# Kord_Kontroller_PCB_0_1.net
KiCad netlist of a schematic drawn in EAGLE
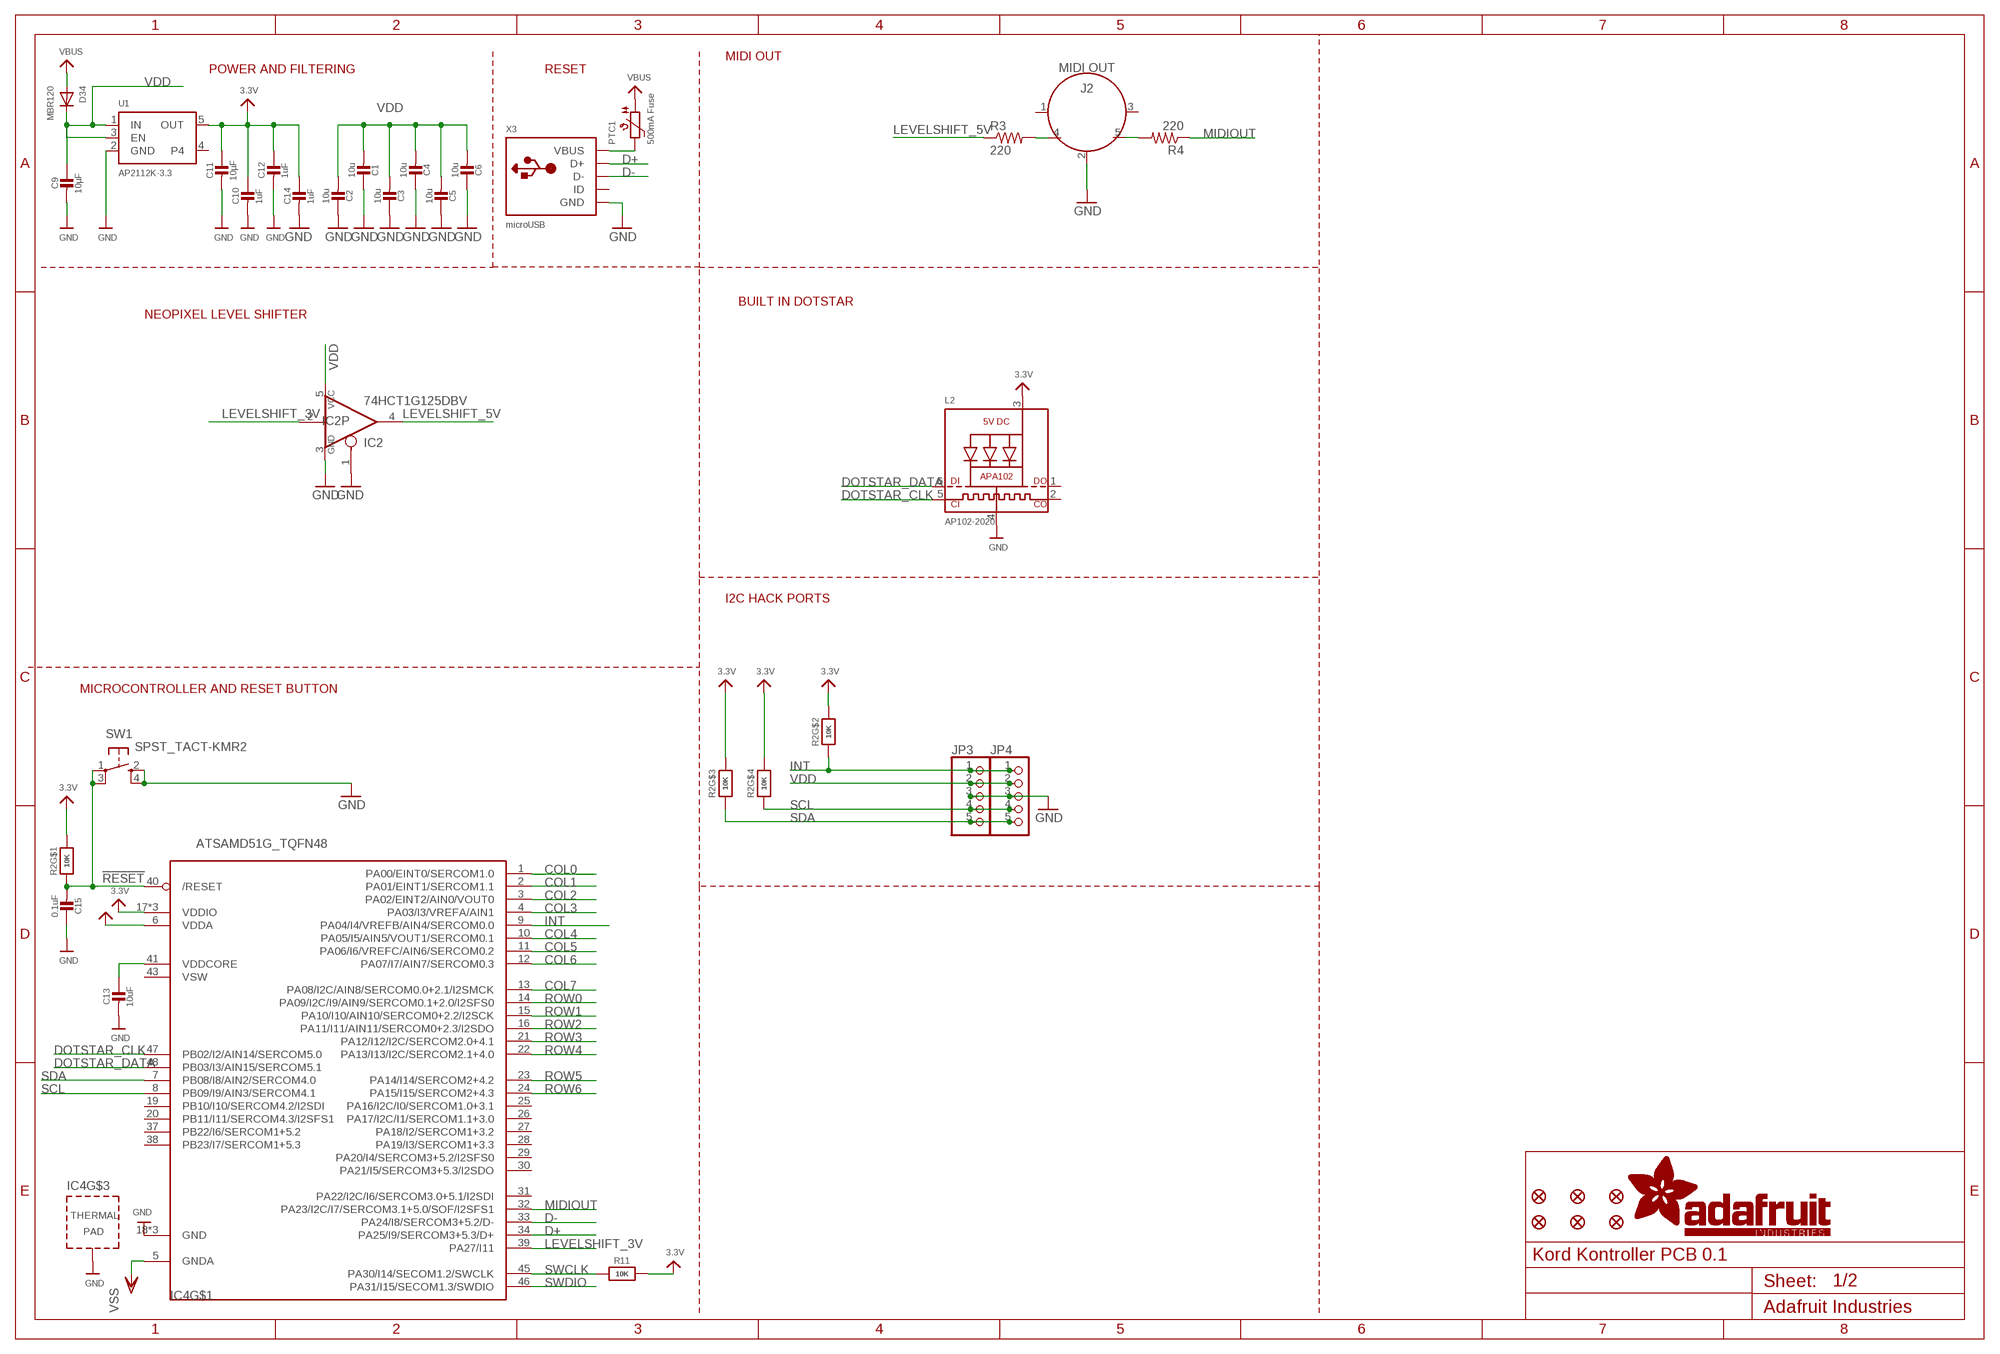
[diagram p0: schematic, sheet 1]
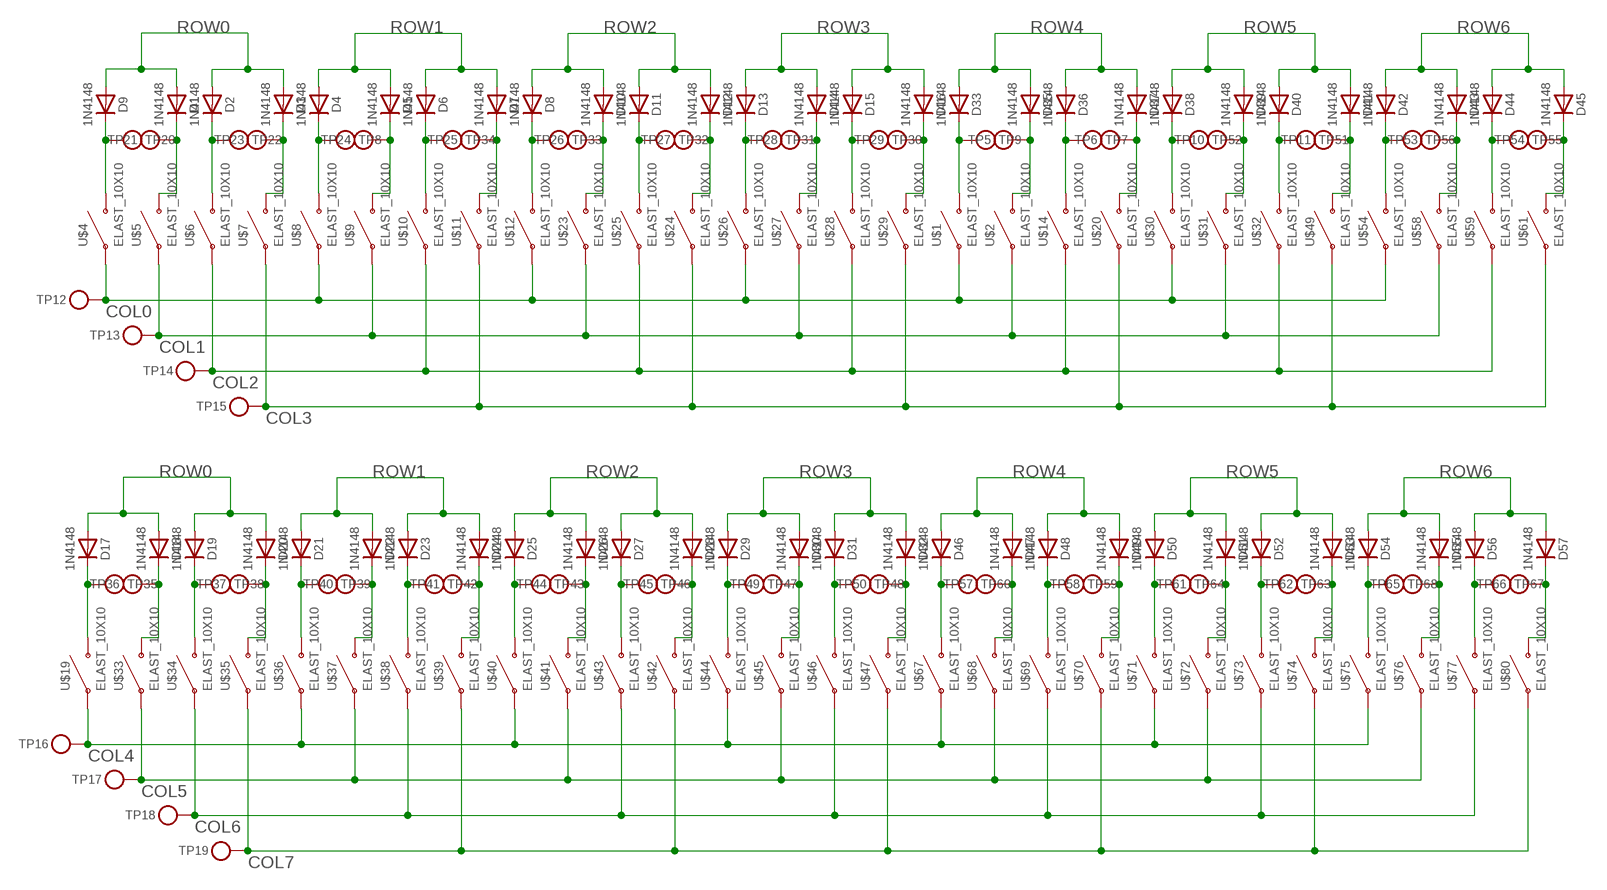
[diagram p1: schematic, sheet 2, part 1 of 2]
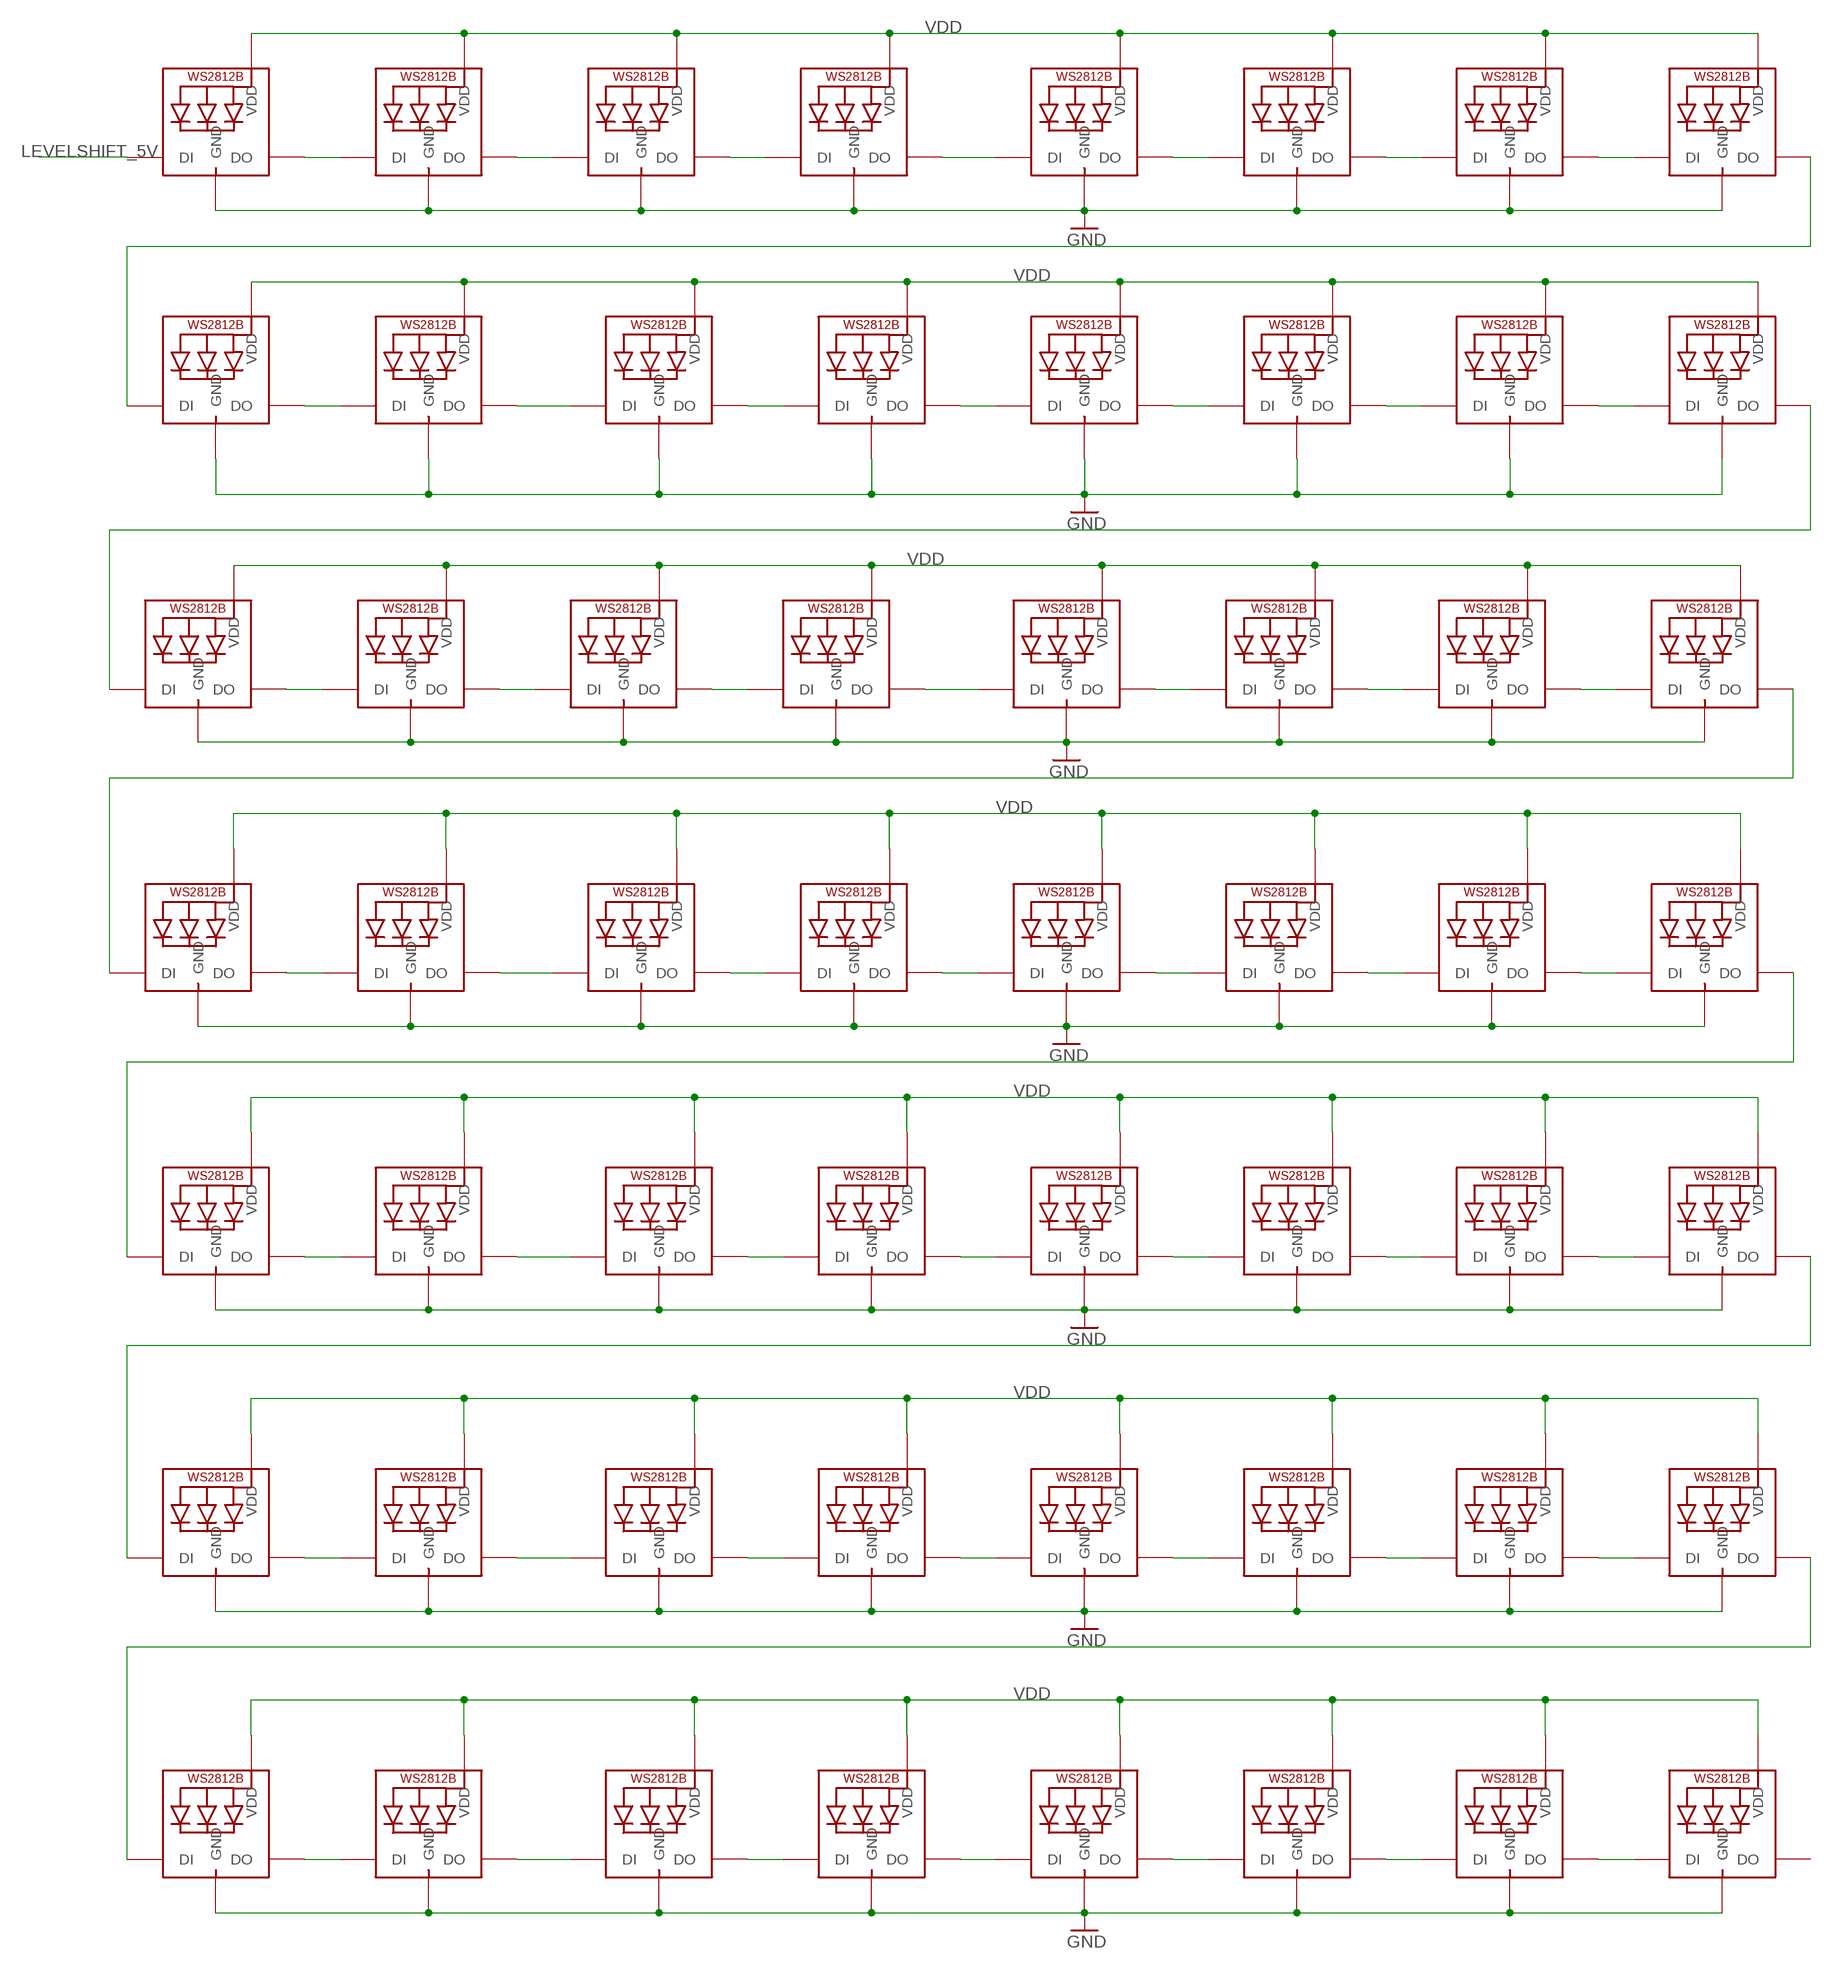
[diagram p2: schematic, sheet 2, part 2 of 2]

(export (version "E")
  (design (tool "Eeschema 10.0.6"))
  (components
    (comp (ref "C1")
      (value "10u")
      (footprint "eagle-import:0805-NO")
      (libsource (lib "eagle-import") (part "CAP_CERAMIC0805-NOOUTLINE"))
    )
    (comp (ref "C2")
      (value "10u")
      (footprint "eagle-import:0805-NO")
      (libsource (lib "eagle-import") (part "CAP_CERAMIC0805-NOOUTLINE"))
    )
    (comp (ref "C3")
      (value "10u")
      (footprint "eagle-import:0805-NO")
      (libsource (lib "eagle-import") (part "CAP_CERAMIC0805-NOOUTLINE"))
    )
    (comp (ref "C4")
      (value "10u")
      (footprint "eagle-import:0805-NO")
      (libsource (lib "eagle-import") (part "CAP_CERAMIC0805-NOOUTLINE"))
    )
    (comp (ref "C5")
      (value "10u")
      (footprint "eagle-import:0805-NO")
      (libsource (lib "eagle-import") (part "CAP_CERAMIC0805-NOOUTLINE"))
    )
    (comp (ref "C6")
      (value "10u")
      (footprint "eagle-import:0805-NO")
      (libsource (lib "eagle-import") (part "CAP_CERAMIC0805-NOOUTLINE"))
    )
    (comp (ref "C9")
      (value "10µF")
      (footprint "eagle-import:0805-NO")
      (libsource (lib "eagle-import") (part "CAP_CERAMIC0805-NOOUTLINE"))
    )
    (comp (ref "C10")
      (value "1uF")
      (footprint "eagle-import:0603-NO")
      (libsource (lib "eagle-import") (part "CAP_CERAMIC0603_NO"))
    )
    (comp (ref "C11")
      (value "10µF")
      (footprint "eagle-import:0805-NO")
      (libsource (lib "eagle-import") (part "CAP_CERAMIC0805-NOOUTLINE"))
    )
    (comp (ref "C12")
      (value "1uF")
      (footprint "eagle-import:0603-NO")
      (libsource (lib "eagle-import") (part "CAP_CERAMIC0603_NO"))
    )
    (comp (ref "C13")
      (value "10uF")
      (footprint "eagle-import:0805-NO")
      (libsource (lib "eagle-import") (part "CAP_CERAMIC0805-NOOUTLINE"))
    )
    (comp (ref "C14")
      (value "1uF")
      (footprint "eagle-import:0603-NO")
      (libsource (lib "eagle-import") (part "CAP_CERAMIC0603_NO"))
    )
    (comp (ref "C15")
      (value "0.1uF")
      (footprint "eagle-import:0603-NO")
      (libsource (lib "eagle-import") (part "CAP_CERAMIC0603_NO"))
    )
    (comp (ref "D34")
      (value "MBR120")
      (footprint "eagle-import:SOD-123FL")
      (libsource (lib "eagle-import") (part "DIODE_SOD-123FL"))
    )
    (comp (ref "FID1")
      (value "FIDUCIAL_1MM")
      (footprint "eagle-import:FIDUCIAL_1MM")
      (libsource (lib "eagle-import") (part "FIDUCIAL_1MM"))
    )
    (comp (ref "FID2")
      (value "FIDUCIAL_1MM")
      (footprint "eagle-import:FIDUCIAL_1MM")
      (libsource (lib "eagle-import") (part "FIDUCIAL_1MM"))
    )
    (comp (ref "FID3")
      (value "FIDUCIAL_1MM")
      (footprint "eagle-import:FIDUCIAL_1MM")
      (libsource (lib "eagle-import") (part "FIDUCIAL_1MM"))
    )
    (comp (ref "FID4")
      (value "FIDUCIAL_1MM")
      (footprint "eagle-import:FIDUCIAL_1MM")
      (libsource (lib "eagle-import") (part "FIDUCIAL_1MM"))
    )
    (comp (ref "FID5")
      (value "FIDUCIAL_1MM")
      (footprint "eagle-import:FIDUCIAL_1MM")
      (libsource (lib "eagle-import") (part "FIDUCIAL_1MM"))
    )
    (comp (ref "FID6")
      (value "FIDUCIAL_1MM")
      (footprint "eagle-import:FIDUCIAL_1MM")
      (libsource (lib "eagle-import") (part "FIDUCIAL_1MM"))
    )
    (comp (ref "IC2")
      (value "74HCT1G125DBV")
      (footprint "eagle-import:SOT23-5")
      (libsource (lib "eagle-import") (part "741G125DBVAHC"))
    )
    (comp (ref "IC4")
      (value "ATSAMD51G_TQFN48")
      (footprint "eagle-import:TQFN48_7MM")
      (libsource (lib "eagle-import") (part "ATSAMD51G_TQFN48"))
    )
    (comp (ref "J2")
      (value "MIDI OUT")
      (footprint "eagle-import:5-PIN-DIN-RA-PCB-NEW")
      (libsource (lib "eagle-import") (part "5-PIN-CIRCULAR-DINNEW"))
    )
    (comp (ref "JP3")
      (value "HEADER-1X5EDGESMT")
      (footprint "eagle-import:5P_EDGECONNECT")
      (libsource (lib "eagle-import") (part "HEADER-1X5EDGESMT"))
    )
    (comp (ref "JP4")
      (value "HEADER-1X5EDGESMT")
      (footprint "eagle-import:5P_EDGECONNECT")
      (libsource (lib "eagle-import") (part "HEADER-1X5EDGESMT"))
    )
    (comp (ref "L2")
      (value "AP102-2020")
      (footprint "eagle-import:APA102_2020")
      (libsource (lib "eagle-import") (part "APA1022020"))
    )
    (comp (ref "PTC1")
      (value "500mA Fuse")
      (footprint "eagle-import:1206")
      (libsource (lib "eagle-import") (part "PTC1206"))
    )
    (comp (ref "R2")
      (value "10K")
      (footprint "eagle-import:RESPACK_4X0603")
      (libsource (lib "eagle-import") (part "RESISTOR_4PACK"))
    )
    (comp (ref "R3")
      (value "220")
      (footprint "eagle-import:0603-RES")
      (libsource (lib "eagle-import") (part "220OHM-1/10W-1%(0603)"))
    )
    (comp (ref "R4")
      (value "220")
      (footprint "eagle-import:0603-RES")
      (libsource (lib "eagle-import") (part "220OHM-1/10W-1%(0603)"))
    )
    (comp (ref "R11")
      (value "10K")
      (footprint "eagle-import:0603-NO")
      (libsource (lib "eagle-import") (part "RESISTOR_0603_NOOUT"))
    )
    (comp (ref "SW1")
      (value "SPST_TACT-KMR2")
      (footprint "eagle-import:KMR2")
      (libsource (lib "eagle-import") (part "SPST_TACT-KMR2"))
    )
    (comp (ref "U1")
      (value "AP2112K-3.3")
      (footprint "eagle-import:SOT23-5")
      (libsource (lib "eagle-import") (part "VREG_SOT23-5"))
    )
    (comp (ref "X3")
      (value "microUSB")
      (footprint "eagle-import:4UCONN_20329_NARROW")
      (libsource (lib "eagle-import") (part "USB_MICRO_NARROW"))
    )
    (comp (ref "D1")
      (value "1N4148")
      (footprint "eagle-import:SOD-323")
      (libsource (lib "eagle-import") (part "DIODESOD-323"))
    )
    (comp (ref "D2")
      (value "1N4148")
      (footprint "eagle-import:SOD-323")
      (libsource (lib "eagle-import") (part "DIODESOD-323"))
    )
    (comp (ref "D3")
      (value "1N4148")
      (footprint "eagle-import:SOD-323")
      (libsource (lib "eagle-import") (part "DIODESOD-323"))
    )
    (comp (ref "D4")
      (value "1N4148")
      (footprint "eagle-import:SOD-323")
      (libsource (lib "eagle-import") (part "DIODESOD-323"))
    )
    (comp (ref "D5")
      (value "1N4148")
      (footprint "eagle-import:SOD-323")
      (libsource (lib "eagle-import") (part "DIODESOD-323"))
    )
    (comp (ref "D6")
      (value "1N4148")
      (footprint "eagle-import:SOD-323")
      (libsource (lib "eagle-import") (part "DIODESOD-323"))
    )
    (comp (ref "D7")
      (value "1N4148")
      (footprint "eagle-import:SOD-323")
      (libsource (lib "eagle-import") (part "DIODESOD-323"))
    )
    (comp (ref "D8")
      (value "1N4148")
      (footprint "eagle-import:SOD-323")
      (libsource (lib "eagle-import") (part "DIODESOD-323"))
    )
    (comp (ref "D9")
      (value "1N4148")
      (footprint "eagle-import:SOD-323")
      (libsource (lib "eagle-import") (part "DIODESOD-323"))
    )
    (comp (ref "D10")
      (value "1N4148")
      (footprint "eagle-import:SOD-323")
      (libsource (lib "eagle-import") (part "DIODESOD-323"))
    )
    (comp (ref "D11")
      (value "1N4148")
      (footprint "eagle-import:SOD-323")
      (libsource (lib "eagle-import") (part "DIODESOD-323"))
    )
    (comp (ref "D12")
      (value "1N4148")
      (footprint "eagle-import:SOD-323")
      (libsource (lib "eagle-import") (part "DIODESOD-323"))
    )
    (comp (ref "D13")
      (value "1N4148")
      (footprint "eagle-import:SOD-323")
      (libsource (lib "eagle-import") (part "DIODESOD-323"))
    )
    (comp (ref "D14")
      (value "1N4148")
      (footprint "eagle-import:SOD-323")
      (libsource (lib "eagle-import") (part "DIODESOD-323"))
    )
    (comp (ref "D15")
      (value "1N4148")
      (footprint "eagle-import:SOD-323")
      (libsource (lib "eagle-import") (part "DIODESOD-323"))
    )
    (comp (ref "D16")
      (value "1N4148")
      (footprint "eagle-import:SOD-323")
      (libsource (lib "eagle-import") (part "DIODESOD-323"))
    )
    (comp (ref "D17")
      (value "1N4148")
      (footprint "eagle-import:SOD-323")
      (libsource (lib "eagle-import") (part "DIODESOD-323"))
    )
    (comp (ref "D18")
      (value "1N4148")
      (footprint "eagle-import:SOD-323")
      (libsource (lib "eagle-import") (part "DIODESOD-323"))
    )
    (comp (ref "D19")
      (value "1N4148")
      (footprint "eagle-import:SOD-323")
      (libsource (lib "eagle-import") (part "DIODESOD-323"))
    )
    (comp (ref "D20")
      (value "1N4148")
      (footprint "eagle-import:SOD-323")
      (libsource (lib "eagle-import") (part "DIODESOD-323"))
    )
    (comp (ref "D21")
      (value "1N4148")
      (footprint "eagle-import:SOD-323")
      (libsource (lib "eagle-import") (part "DIODESOD-323"))
    )
    (comp (ref "D22")
      (value "1N4148")
      (footprint "eagle-import:SOD-323")
      (libsource (lib "eagle-import") (part "DIODESOD-323"))
    )
    (comp (ref "D23")
      (value "1N4148")
      (footprint "eagle-import:SOD-323")
      (libsource (lib "eagle-import") (part "DIODESOD-323"))
    )
    (comp (ref "D24")
      (value "1N4148")
      (footprint "eagle-import:SOD-323")
      (libsource (lib "eagle-import") (part "DIODESOD-323"))
    )
    (comp (ref "D25")
      (value "1N4148")
      (footprint "eagle-import:SOD-323")
      (libsource (lib "eagle-import") (part "DIODESOD-323"))
    )
    (comp (ref "D26")
      (value "1N4148")
      (footprint "eagle-import:SOD-323")
      (libsource (lib "eagle-import") (part "DIODESOD-323"))
    )
    (comp (ref "D27")
      (value "1N4148")
      (footprint "eagle-import:SOD-323")
      (libsource (lib "eagle-import") (part "DIODESOD-323"))
    )
    (comp (ref "D28")
      (value "1N4148")
      (footprint "eagle-import:SOD-323")
      (libsource (lib "eagle-import") (part "DIODESOD-323"))
    )
    (comp (ref "D29")
      (value "1N4148")
      (footprint "eagle-import:SOD-323")
      (libsource (lib "eagle-import") (part "DIODESOD-323"))
    )
    (comp (ref "D30")
      (value "1N4148")
      (footprint "eagle-import:SOD-323")
      (libsource (lib "eagle-import") (part "DIODESOD-323"))
    )
    (comp (ref "D31")
      (value "1N4148")
      (footprint "eagle-import:SOD-323")
      (libsource (lib "eagle-import") (part "DIODESOD-323"))
    )
    (comp (ref "D32")
      (value "1N4148")
      (footprint "eagle-import:SOD-323")
      (libsource (lib "eagle-import") (part "DIODESOD-323"))
    )
    (comp (ref "D33")
      (value "1N4148")
      (footprint "eagle-import:SOD-323")
      (libsource (lib "eagle-import") (part "DIODESOD-323"))
    )
    (comp (ref "D35")
      (value "1N4148")
      (footprint "eagle-import:SOD-323")
      (libsource (lib "eagle-import") (part "DIODESOD-323"))
    )
    (comp (ref "D36")
      (value "1N4148")
      (footprint "eagle-import:SOD-323")
      (libsource (lib "eagle-import") (part "DIODESOD-323"))
    )
    (comp (ref "D37")
      (value "1N4148")
      (footprint "eagle-import:SOD-323")
      (libsource (lib "eagle-import") (part "DIODESOD-323"))
    )
    (comp (ref "D38")
      (value "1N4148")
      (footprint "eagle-import:SOD-323")
      (libsource (lib "eagle-import") (part "DIODESOD-323"))
    )
    (comp (ref "D39")
      (value "1N4148")
      (footprint "eagle-import:SOD-323")
      (libsource (lib "eagle-import") (part "DIODESOD-323"))
    )
    (comp (ref "D40")
      (value "1N4148")
      (footprint "eagle-import:SOD-323")
      (libsource (lib "eagle-import") (part "DIODESOD-323"))
    )
    (comp (ref "D41")
      (value "1N4148")
      (footprint "eagle-import:SOD-323")
      (libsource (lib "eagle-import") (part "DIODESOD-323"))
    )
    (comp (ref "D42")
      (value "1N4148")
      (footprint "eagle-import:SOD-323")
      (libsource (lib "eagle-import") (part "DIODESOD-323"))
    )
    (comp (ref "D43")
      (value "1N4148")
      (footprint "eagle-import:SOD-323")
      (libsource (lib "eagle-import") (part "DIODESOD-323"))
    )
    (comp (ref "D44")
      (value "1N4148")
      (footprint "eagle-import:SOD-323")
      (libsource (lib "eagle-import") (part "DIODESOD-323"))
    )
    (comp (ref "D45")
      (value "1N4148")
      (footprint "eagle-import:SOD-323")
      (libsource (lib "eagle-import") (part "DIODESOD-323"))
    )
    (comp (ref "D46")
      (value "1N4148")
      (footprint "eagle-import:SOD-323")
      (libsource (lib "eagle-import") (part "DIODESOD-323"))
    )
    (comp (ref "D47")
      (value "1N4148")
      (footprint "eagle-import:SOD-323")
      (libsource (lib "eagle-import") (part "DIODESOD-323"))
    )
    (comp (ref "D48")
      (value "1N4148")
      (footprint "eagle-import:SOD-323")
      (libsource (lib "eagle-import") (part "DIODESOD-323"))
    )
    (comp (ref "D49")
      (value "1N4148")
      (footprint "eagle-import:SOD-323")
      (libsource (lib "eagle-import") (part "DIODESOD-323"))
    )
    (comp (ref "D50")
      (value "1N4148")
      (footprint "eagle-import:SOD-323")
      (libsource (lib "eagle-import") (part "DIODESOD-323"))
    )
    (comp (ref "D51")
      (value "1N4148")
      (footprint "eagle-import:SOD-323")
      (libsource (lib "eagle-import") (part "DIODESOD-323"))
    )
    (comp (ref "D52")
      (value "1N4148")
      (footprint "eagle-import:SOD-323")
      (libsource (lib "eagle-import") (part "DIODESOD-323"))
    )
    (comp (ref "D53")
      (value "1N4148")
      (footprint "eagle-import:SOD-323")
      (libsource (lib "eagle-import") (part "DIODESOD-323"))
    )
    (comp (ref "D54")
      (value "1N4148")
      (footprint "eagle-import:SOD-323")
      (libsource (lib "eagle-import") (part "DIODESOD-323"))
    )
    (comp (ref "D55")
      (value "1N4148")
      (footprint "eagle-import:SOD-323")
      (libsource (lib "eagle-import") (part "DIODESOD-323"))
    )
    (comp (ref "D56")
      (value "1N4148")
      (footprint "eagle-import:SOD-323")
      (libsource (lib "eagle-import") (part "DIODESOD-323"))
    )
    (comp (ref "D57")
      (value "1N4148")
      (footprint "eagle-import:SOD-323")
      (libsource (lib "eagle-import") (part "DIODESOD-323"))
    )
    (comp (ref "LED1")
      (value "WS2812B3535")
      (footprint "eagle-import:LED3535")
      (libsource (lib "eagle-import") (part "WS2812B3535"))
    )
    (comp (ref "LED2")
      (value "WS2812B3535")
      (footprint "eagle-import:LED3535")
      (libsource (lib "eagle-import") (part "WS2812B3535"))
    )
    (comp (ref "LED3")
      (value "WS2812B3535")
      (footprint "eagle-import:LED3535")
      (libsource (lib "eagle-import") (part "WS2812B3535"))
    )
    (comp (ref "LED4")
      (value "WS2812B3535")
      (footprint "eagle-import:LED3535")
      (libsource (lib "eagle-import") (part "WS2812B3535"))
    )
    (comp (ref "LED5")
      (value "WS2812B3535")
      (footprint "eagle-import:LED3535")
      (libsource (lib "eagle-import") (part "WS2812B3535"))
    )
    (comp (ref "LED6")
      (value "WS2812B3535")
      (footprint "eagle-import:LED3535")
      (libsource (lib "eagle-import") (part "WS2812B3535"))
    )
    (comp (ref "LED7")
      (value "WS2812B3535")
      (footprint "eagle-import:LED3535")
      (libsource (lib "eagle-import") (part "WS2812B3535"))
    )
    (comp (ref "LED8")
      (value "WS2812B3535")
      (footprint "eagle-import:LED3535")
      (libsource (lib "eagle-import") (part "WS2812B3535"))
    )
    (comp (ref "LED9")
      (value "WS2812B3535")
      (footprint "eagle-import:LED3535")
      (libsource (lib "eagle-import") (part "WS2812B3535"))
    )
    (comp (ref "LED10")
      (value "WS2812B3535")
      (footprint "eagle-import:LED3535")
      (libsource (lib "eagle-import") (part "WS2812B3535"))
    )
    (comp (ref "LED11")
      (value "WS2812B3535")
      (footprint "eagle-import:LED3535")
      (libsource (lib "eagle-import") (part "WS2812B3535"))
    )
    (comp (ref "LED12")
      (value "WS2812B3535")
      (footprint "eagle-import:LED3535")
      (libsource (lib "eagle-import") (part "WS2812B3535"))
    )
    (comp (ref "LED13")
      (value "WS2812B3535")
      (footprint "eagle-import:LED3535")
      (libsource (lib "eagle-import") (part "WS2812B3535"))
    )
    (comp (ref "LED14")
      (value "WS2812B3535")
      (footprint "eagle-import:LED3535")
      (libsource (lib "eagle-import") (part "WS2812B3535"))
    )
    (comp (ref "LED15")
      (value "WS2812B3535")
      (footprint "eagle-import:LED3535")
      (libsource (lib "eagle-import") (part "WS2812B3535"))
    )
    (comp (ref "LED16")
      (value "WS2812B3535")
      (footprint "eagle-import:LED3535")
      (libsource (lib "eagle-import") (part "WS2812B3535"))
    )
    (comp (ref "LED17")
      (value "WS2812B3535")
      (footprint "eagle-import:LED3535")
      (libsource (lib "eagle-import") (part "WS2812B3535"))
    )
    (comp (ref "LED18")
      (value "WS2812B3535")
      (footprint "eagle-import:LED3535")
      (libsource (lib "eagle-import") (part "WS2812B3535"))
    )
    (comp (ref "LED19")
      (value "WS2812B3535")
      (footprint "eagle-import:LED3535")
      (libsource (lib "eagle-import") (part "WS2812B3535"))
    )
    (comp (ref "LED20")
      (value "WS2812B3535")
      (footprint "eagle-import:LED3535")
      (libsource (lib "eagle-import") (part "WS2812B3535"))
    )
    (comp (ref "LED21")
      (value "WS2812B3535")
      (footprint "eagle-import:LED3535")
      (libsource (lib "eagle-import") (part "WS2812B3535"))
    )
    (comp (ref "LED22")
      (value "WS2812B3535")
      (footprint "eagle-import:LED3535")
      (libsource (lib "eagle-import") (part "WS2812B3535"))
    )
    (comp (ref "LED23")
      (value "WS2812B3535")
      (footprint "eagle-import:LED3535")
      (libsource (lib "eagle-import") (part "WS2812B3535"))
    )
    (comp (ref "LED24")
      (value "WS2812B3535")
      (footprint "eagle-import:LED3535")
      (libsource (lib "eagle-import") (part "WS2812B3535"))
    )
    (comp (ref "LED25")
      (value "WS2812B3535")
      (footprint "eagle-import:LED3535")
      (libsource (lib "eagle-import") (part "WS2812B3535"))
    )
    (comp (ref "LED26")
      (value "WS2812B3535")
      (footprint "eagle-import:LED3535")
      (libsource (lib "eagle-import") (part "WS2812B3535"))
    )
    (comp (ref "LED27")
      (value "WS2812B3535")
      (footprint "eagle-import:LED3535")
      (libsource (lib "eagle-import") (part "WS2812B3535"))
    )
    (comp (ref "LED28")
      (value "WS2812B3535")
      (footprint "eagle-import:LED3535")
      (libsource (lib "eagle-import") (part "WS2812B3535"))
    )
    (comp (ref "LED29")
      (value "WS2812B3535")
      (footprint "eagle-import:LED3535")
      (libsource (lib "eagle-import") (part "WS2812B3535"))
    )
    (comp (ref "LED30")
      (value "WS2812B3535")
      (footprint "eagle-import:LED3535")
      (libsource (lib "eagle-import") (part "WS2812B3535"))
    )
    (comp (ref "LED31")
      (value "WS2812B3535")
      (footprint "eagle-import:LED3535")
      (libsource (lib "eagle-import") (part "WS2812B3535"))
    )
    (comp (ref "LED32")
      (value "WS2812B3535")
      (footprint "eagle-import:LED3535")
      (libsource (lib "eagle-import") (part "WS2812B3535"))
    )
    (comp (ref "LED33")
      (value "WS2812B3535")
      (footprint "eagle-import:LED3535")
      (libsource (lib "eagle-import") (part "WS2812B3535"))
    )
    (comp (ref "LED34")
      (value "WS2812B3535")
      (footprint "eagle-import:LED3535")
      (libsource (lib "eagle-import") (part "WS2812B3535"))
    )
    (comp (ref "LED35")
      (value "WS2812B3535")
      (footprint "eagle-import:LED3535")
      (libsource (lib "eagle-import") (part "WS2812B3535"))
    )
    (comp (ref "LED36")
      (value "WS2812B3535")
      (footprint "eagle-import:LED3535")
      (libsource (lib "eagle-import") (part "WS2812B3535"))
    )
    (comp (ref "LED37")
      (value "WS2812B3535")
      (footprint "eagle-import:LED3535")
      (libsource (lib "eagle-import") (part "WS2812B3535"))
    )
    (comp (ref "LED38")
      (value "WS2812B3535")
      (footprint "eagle-import:LED3535")
      (libsource (lib "eagle-import") (part "WS2812B3535"))
    )
    (comp (ref "LED39")
      (value "WS2812B3535")
      (footprint "eagle-import:LED3535")
      (libsource (lib "eagle-import") (part "WS2812B3535"))
    )
    (comp (ref "LED40")
      (value "WS2812B3535")
      (footprint "eagle-import:LED3535")
      (libsource (lib "eagle-import") (part "WS2812B3535"))
    )
    (comp (ref "LED41")
      (value "WS2812B3535")
      (footprint "eagle-import:LED3535")
      (libsource (lib "eagle-import") (part "WS2812B3535"))
    )
    (comp (ref "LED42")
      (value "WS2812B3535")
      (footprint "eagle-import:LED3535")
      (libsource (lib "eagle-import") (part "WS2812B3535"))
    )
    (comp (ref "LED43")
      (value "WS2812B3535")
      (footprint "eagle-import:LED3535")
      (libsource (lib "eagle-import") (part "WS2812B3535"))
    )
    (comp (ref "LED44")
      (value "WS2812B3535")
      (footprint "eagle-import:LED3535")
      (libsource (lib "eagle-import") (part "WS2812B3535"))
    )
    (comp (ref "LED45")
      (value "WS2812B3535")
      (footprint "eagle-import:LED3535")
      (libsource (lib "eagle-import") (part "WS2812B3535"))
    )
    (comp (ref "LED46")
      (value "WS2812B3535")
      (footprint "eagle-import:LED3535")
      (libsource (lib "eagle-import") (part "WS2812B3535"))
    )
    (comp (ref "LED47")
      (value "WS2812B3535")
      (footprint "eagle-import:LED3535")
      (libsource (lib "eagle-import") (part "WS2812B3535"))
    )
    (comp (ref "LED48")
      (value "WS2812B3535")
      (footprint "eagle-import:LED3535")
      (libsource (lib "eagle-import") (part "WS2812B3535"))
    )
    (comp (ref "LED49")
      (value "WS2812B3535")
      (footprint "eagle-import:LED3535")
      (libsource (lib "eagle-import") (part "WS2812B3535"))
    )
    (comp (ref "LED50")
      (value "WS2812B3535")
      (footprint "eagle-import:LED3535")
      (libsource (lib "eagle-import") (part "WS2812B3535"))
    )
    (comp (ref "LED51")
      (value "WS2812B3535")
      (footprint "eagle-import:LED3535")
      (libsource (lib "eagle-import") (part "WS2812B3535"))
    )
    (comp (ref "LED52")
      (value "WS2812B3535")
      (footprint "eagle-import:LED3535")
      (libsource (lib "eagle-import") (part "WS2812B3535"))
    )
    (comp (ref "LED53")
      (value "WS2812B3535")
      (footprint "eagle-import:LED3535")
      (libsource (lib "eagle-import") (part "WS2812B3535"))
    )
    (comp (ref "LED54")
      (value "WS2812B3535")
      (footprint "eagle-import:LED3535")
      (libsource (lib "eagle-import") (part "WS2812B3535"))
    )
    (comp (ref "LED55")
      (value "WS2812B3535")
      (footprint "eagle-import:LED3535")
      (libsource (lib "eagle-import") (part "WS2812B3535"))
    )
    (comp (ref "LED56")
      (value "WS2812B3535")
      (footprint "eagle-import:LED3535")
      (libsource (lib "eagle-import") (part "WS2812B3535"))
    )
    (comp (ref "TP5")
      (value "TESTPOINTROUND1.5MM")
      (footprint "eagle-import:TESTPOINT_ROUND_1.5MM")
      (libsource (lib "eagle-import") (part "TESTPOINTROUND1.5MM"))
    )
    (comp (ref "TP6")
      (value "TESTPOINTROUND1.5MM")
      (footprint "eagle-import:TESTPOINT_ROUND_1.5MM")
      (libsource (lib "eagle-import") (part "TESTPOINTROUND1.5MM"))
    )
    (comp (ref "TP7")
      (value "TESTPOINTROUND1.5MM")
      (footprint "eagle-import:TESTPOINT_ROUND_1.5MM")
      (libsource (lib "eagle-import") (part "TESTPOINTROUND1.5MM"))
    )
    (comp (ref "TP8")
      (value "TESTPOINTROUND1.5MM")
      (footprint "eagle-import:TESTPOINT_ROUND_1.5MM")
      (libsource (lib "eagle-import") (part "TESTPOINTROUND1.5MM"))
    )
    (comp (ref "TP9")
      (value "TESTPOINTROUND1.5MM")
      (footprint "eagle-import:TESTPOINT_ROUND_1.5MM")
      (libsource (lib "eagle-import") (part "TESTPOINTROUND1.5MM"))
    )
    (comp (ref "TP10")
      (value "TESTPOINTROUND1.5MM")
      (footprint "eagle-import:TESTPOINT_ROUND_1.5MM")
      (libsource (lib "eagle-import") (part "TESTPOINTROUND1.5MM"))
    )
    (comp (ref "TP11")
      (value "TESTPOINTROUND1.5MM")
      (footprint "eagle-import:TESTPOINT_ROUND_1.5MM")
      (libsource (lib "eagle-import") (part "TESTPOINTROUND1.5MM"))
    )
    (comp (ref "TP12")
      (value "TESTPOINTROUND1.5MM")
      (footprint "eagle-import:TESTPOINT_ROUND_1.5MM")
      (libsource (lib "eagle-import") (part "TESTPOINTROUND1.5MM"))
    )
    (comp (ref "TP13")
      (value "TESTPOINTROUND1.5MM")
      (footprint "eagle-import:TESTPOINT_ROUND_1.5MM")
      (libsource (lib "eagle-import") (part "TESTPOINTROUND1.5MM"))
    )
    (comp (ref "TP14")
      (value "TESTPOINTROUND1.5MM")
      (footprint "eagle-import:TESTPOINT_ROUND_1.5MM")
      (libsource (lib "eagle-import") (part "TESTPOINTROUND1.5MM"))
    )
    (comp (ref "TP15")
      (value "TESTPOINTROUND1.5MM")
      (footprint "eagle-import:TESTPOINT_ROUND_1.5MM")
      (libsource (lib "eagle-import") (part "TESTPOINTROUND1.5MM"))
    )
    (comp (ref "TP16")
      (value "TESTPOINTROUND1.5MM")
      (footprint "eagle-import:TESTPOINT_ROUND_1.5MM")
      (libsource (lib "eagle-import") (part "TESTPOINTROUND1.5MM"))
    )
    (comp (ref "TP17")
      (value "TESTPOINTROUND1.5MM")
      (footprint "eagle-import:TESTPOINT_ROUND_1.5MM")
      (libsource (lib "eagle-import") (part "TESTPOINTROUND1.5MM"))
    )
    (comp (ref "TP18")
      (value "TESTPOINTROUND1.5MM")
      (footprint "eagle-import:TESTPOINT_ROUND_1.5MM")
      (libsource (lib "eagle-import") (part "TESTPOINTROUND1.5MM"))
    )
    (comp (ref "TP19")
      (value "TESTPOINTROUND1.5MM")
      (footprint "eagle-import:TESTPOINT_ROUND_1.5MM")
      (libsource (lib "eagle-import") (part "TESTPOINTROUND1.5MM"))
    )
    (comp (ref "TP20")
      (value "TESTPOINTROUND1.5MM")
      (footprint "eagle-import:TESTPOINT_ROUND_1.5MM")
      (libsource (lib "eagle-import") (part "TESTPOINTROUND1.5MM"))
    )
    (comp (ref "TP21")
      (value "TESTPOINTROUND1.5MM")
      (footprint "eagle-import:TESTPOINT_ROUND_1.5MM")
      (libsource (lib "eagle-import") (part "TESTPOINTROUND1.5MM"))
    )
    (comp (ref "TP22")
      (value "TESTPOINTROUND1.5MM")
      (footprint "eagle-import:TESTPOINT_ROUND_1.5MM")
      (libsource (lib "eagle-import") (part "TESTPOINTROUND1.5MM"))
    )
    (comp (ref "TP23")
      (value "TESTPOINTROUND1.5MM")
      (footprint "eagle-import:TESTPOINT_ROUND_1.5MM")
      (libsource (lib "eagle-import") (part "TESTPOINTROUND1.5MM"))
    )
    (comp (ref "TP24")
      (value "TESTPOINTROUND1.5MM")
      (footprint "eagle-import:TESTPOINT_ROUND_1.5MM")
      (libsource (lib "eagle-import") (part "TESTPOINTROUND1.5MM"))
    )
    (comp (ref "TP25")
      (value "TESTPOINTROUND1.5MM")
      (footprint "eagle-import:TESTPOINT_ROUND_1.5MM")
      (libsource (lib "eagle-import") (part "TESTPOINTROUND1.5MM"))
    )
    (comp (ref "TP26")
      (value "TESTPOINTROUND1.5MM")
      (footprint "eagle-import:TESTPOINT_ROUND_1.5MM")
      (libsource (lib "eagle-import") (part "TESTPOINTROUND1.5MM"))
    )
    (comp (ref "TP27")
      (value "TESTPOINTROUND1.5MM")
      (footprint "eagle-import:TESTPOINT_ROUND_1.5MM")
      (libsource (lib "eagle-import") (part "TESTPOINTROUND1.5MM"))
    )
    (comp (ref "TP28")
      (value "TESTPOINTROUND1.5MM")
      (footprint "eagle-import:TESTPOINT_ROUND_1.5MM")
      (libsource (lib "eagle-import") (part "TESTPOINTROUND1.5MM"))
    )
    (comp (ref "TP29")
      (value "TESTPOINTROUND1.5MM")
      (footprint "eagle-import:TESTPOINT_ROUND_1.5MM")
      (libsource (lib "eagle-import") (part "TESTPOINTROUND1.5MM"))
    )
    (comp (ref "TP30")
      (value "TESTPOINTROUND1.5MM")
      (footprint "eagle-import:TESTPOINT_ROUND_1.5MM")
      (libsource (lib "eagle-import") (part "TESTPOINTROUND1.5MM"))
    )
    (comp (ref "TP31")
      (value "TESTPOINTROUND1.5MM")
      (footprint "eagle-import:TESTPOINT_ROUND_1.5MM")
      (libsource (lib "eagle-import") (part "TESTPOINTROUND1.5MM"))
    )
    (comp (ref "TP32")
      (value "TESTPOINTROUND1.5MM")
      (footprint "eagle-import:TESTPOINT_ROUND_1.5MM")
      (libsource (lib "eagle-import") (part "TESTPOINTROUND1.5MM"))
    )
    (comp (ref "TP33")
      (value "TESTPOINTROUND1.5MM")
      (footprint "eagle-import:TESTPOINT_ROUND_1.5MM")
      (libsource (lib "eagle-import") (part "TESTPOINTROUND1.5MM"))
    )
    (comp (ref "TP34")
      (value "TESTPOINTROUND1.5MM")
      (footprint "eagle-import:TESTPOINT_ROUND_1.5MM")
      (libsource (lib "eagle-import") (part "TESTPOINTROUND1.5MM"))
    )
    (comp (ref "TP35")
      (value "TESTPOINTROUND1.5MM")
      (footprint "eagle-import:TESTPOINT_ROUND_1.5MM")
      (libsource (lib "eagle-import") (part "TESTPOINTROUND1.5MM"))
    )
    (comp (ref "TP36")
      (value "TESTPOINTROUND1.5MM")
      (footprint "eagle-import:TESTPOINT_ROUND_1.5MM")
      (libsource (lib "eagle-import") (part "TESTPOINTROUND1.5MM"))
    )
    (comp (ref "TP37")
      (value "TESTPOINTROUND1.5MM")
      (footprint "eagle-import:TESTPOINT_ROUND_1.5MM")
      (libsource (lib "eagle-import") (part "TESTPOINTROUND1.5MM"))
    )
    (comp (ref "TP38")
      (value "TESTPOINTROUND1.5MM")
      (footprint "eagle-import:TESTPOINT_ROUND_1.5MM")
      (libsource (lib "eagle-import") (part "TESTPOINTROUND1.5MM"))
    )
    (comp (ref "TP39")
      (value "TESTPOINTROUND1.5MM")
      (footprint "eagle-import:TESTPOINT_ROUND_1.5MM")
      (libsource (lib "eagle-import") (part "TESTPOINTROUND1.5MM"))
    )
    (comp (ref "TP40")
      (value "TESTPOINTROUND1.5MM")
      (footprint "eagle-import:TESTPOINT_ROUND_1.5MM")
      (libsource (lib "eagle-import") (part "TESTPOINTROUND1.5MM"))
    )
    (comp (ref "TP41")
      (value "TESTPOINTROUND1.5MM")
      (footprint "eagle-import:TESTPOINT_ROUND_1.5MM")
      (libsource (lib "eagle-import") (part "TESTPOINTROUND1.5MM"))
    )
    (comp (ref "TP42")
      (value "TESTPOINTROUND1.5MM")
      (footprint "eagle-import:TESTPOINT_ROUND_1.5MM")
      (libsource (lib "eagle-import") (part "TESTPOINTROUND1.5MM"))
    )
    (comp (ref "TP43")
      (value "TESTPOINTROUND1.5MM")
      (footprint "eagle-import:TESTPOINT_ROUND_1.5MM")
      (libsource (lib "eagle-import") (part "TESTPOINTROUND1.5MM"))
    )
    (comp (ref "TP44")
      (value "TESTPOINTROUND1.5MM")
      (footprint "eagle-import:TESTPOINT_ROUND_1.5MM")
      (libsource (lib "eagle-import") (part "TESTPOINTROUND1.5MM"))
    )
    (comp (ref "TP45")
      (value "TESTPOINTROUND1.5MM")
      (footprint "eagle-import:TESTPOINT_ROUND_1.5MM")
      (libsource (lib "eagle-import") (part "TESTPOINTROUND1.5MM"))
    )
    (comp (ref "TP46")
      (value "TESTPOINTROUND1.5MM")
      (footprint "eagle-import:TESTPOINT_ROUND_1.5MM")
      (libsource (lib "eagle-import") (part "TESTPOINTROUND1.5MM"))
    )
    (comp (ref "TP47")
      (value "TESTPOINTROUND1.5MM")
      (footprint "eagle-import:TESTPOINT_ROUND_1.5MM")
      (libsource (lib "eagle-import") (part "TESTPOINTROUND1.5MM"))
    )
    (comp (ref "TP48")
      (value "TESTPOINTROUND1.5MM")
      (footprint "eagle-import:TESTPOINT_ROUND_1.5MM")
      (libsource (lib "eagle-import") (part "TESTPOINTROUND1.5MM"))
    )
    (comp (ref "TP49")
      (value "TESTPOINTROUND1.5MM")
      (footprint "eagle-import:TESTPOINT_ROUND_1.5MM")
      (libsource (lib "eagle-import") (part "TESTPOINTROUND1.5MM"))
    )
    (comp (ref "TP50")
      (value "TESTPOINTROUND1.5MM")
      (footprint "eagle-import:TESTPOINT_ROUND_1.5MM")
      (libsource (lib "eagle-import") (part "TESTPOINTROUND1.5MM"))
    )
    (comp (ref "TP51")
      (value "TESTPOINTROUND1.5MM")
      (footprint "eagle-import:TESTPOINT_ROUND_1.5MM")
      (libsource (lib "eagle-import") (part "TESTPOINTROUND1.5MM"))
    )
    (comp (ref "TP52")
      (value "TESTPOINTROUND1.5MM")
      (footprint "eagle-import:TESTPOINT_ROUND_1.5MM")
      (libsource (lib "eagle-import") (part "TESTPOINTROUND1.5MM"))
    )
    (comp (ref "TP53")
      (value "TESTPOINTROUND1.5MM")
      (footprint "eagle-import:TESTPOINT_ROUND_1.5MM")
      (libsource (lib "eagle-import") (part "TESTPOINTROUND1.5MM"))
    )
    (comp (ref "TP54")
      (value "TESTPOINTROUND1.5MM")
      (footprint "eagle-import:TESTPOINT_ROUND_1.5MM")
      (libsource (lib "eagle-import") (part "TESTPOINTROUND1.5MM"))
    )
    (comp (ref "TP55")
      (value "TESTPOINTROUND1.5MM")
      (footprint "eagle-import:TESTPOINT_ROUND_1.5MM")
      (libsource (lib "eagle-import") (part "TESTPOINTROUND1.5MM"))
    )
    (comp (ref "TP56")
      (value "TESTPOINTROUND1.5MM")
      (footprint "eagle-import:TESTPOINT_ROUND_1.5MM")
      (libsource (lib "eagle-import") (part "TESTPOINTROUND1.5MM"))
    )
    (comp (ref "TP57")
      (value "TESTPOINTROUND1.5MM")
      (footprint "eagle-import:TESTPOINT_ROUND_1.5MM")
      (libsource (lib "eagle-import") (part "TESTPOINTROUND1.5MM"))
    )
    (comp (ref "TP58")
      (value "TESTPOINTROUND1.5MM")
      (footprint "eagle-import:TESTPOINT_ROUND_1.5MM")
      (libsource (lib "eagle-import") (part "TESTPOINTROUND1.5MM"))
    )
    (comp (ref "TP59")
      (value "TESTPOINTROUND1.5MM")
      (footprint "eagle-import:TESTPOINT_ROUND_1.5MM")
      (libsource (lib "eagle-import") (part "TESTPOINTROUND1.5MM"))
    )
    (comp (ref "TP60")
      (value "TESTPOINTROUND1.5MM")
      (footprint "eagle-import:TESTPOINT_ROUND_1.5MM")
      (libsource (lib "eagle-import") (part "TESTPOINTROUND1.5MM"))
    )
    (comp (ref "TP61")
      (value "TESTPOINTROUND1.5MM")
      (footprint "eagle-import:TESTPOINT_ROUND_1.5MM")
      (libsource (lib "eagle-import") (part "TESTPOINTROUND1.5MM"))
    )
    (comp (ref "TP62")
      (value "TESTPOINTROUND1.5MM")
      (footprint "eagle-import:TESTPOINT_ROUND_1.5MM")
      (libsource (lib "eagle-import") (part "TESTPOINTROUND1.5MM"))
    )
    (comp (ref "TP63")
      (value "TESTPOINTROUND1.5MM")
      (footprint "eagle-import:TESTPOINT_ROUND_1.5MM")
      (libsource (lib "eagle-import") (part "TESTPOINTROUND1.5MM"))
    )
    (comp (ref "TP64")
      (value "TESTPOINTROUND1.5MM")
      (footprint "eagle-import:TESTPOINT_ROUND_1.5MM")
      (libsource (lib "eagle-import") (part "TESTPOINTROUND1.5MM"))
    )
    (comp (ref "TP65")
      (value "TESTPOINTROUND1.5MM")
      (footprint "eagle-import:TESTPOINT_ROUND_1.5MM")
      (libsource (lib "eagle-import") (part "TESTPOINTROUND1.5MM"))
    )
    (comp (ref "TP66")
      (value "TESTPOINTROUND1.5MM")
      (footprint "eagle-import:TESTPOINT_ROUND_1.5MM")
      (libsource (lib "eagle-import") (part "TESTPOINTROUND1.5MM"))
    )
    (comp (ref "TP67")
      (value "TESTPOINTROUND1.5MM")
      (footprint "eagle-import:TESTPOINT_ROUND_1.5MM")
      (libsource (lib "eagle-import") (part "TESTPOINTROUND1.5MM"))
    )
    (comp (ref "TP68")
      (value "TESTPOINTROUND1.5MM")
      (footprint "eagle-import:TESTPOINT_ROUND_1.5MM")
      (libsource (lib "eagle-import") (part "TESTPOINTROUND1.5MM"))
    )
    (comp (ref "U$1")
      (value "ELAST_10X10")
      (footprint "eagle-import:ELAST_PAD_SQUARE_10MM_4X4WIDE")
      (libsource (lib "eagle-import") (part "ELAST_10X10"))
    )
    (comp (ref "U$2")
      (value "ELAST_10X10")
      (footprint "eagle-import:ELAST_PAD_SQUARE_10MM_4X4WIDE")
      (libsource (lib "eagle-import") (part "ELAST_10X10"))
    )
    (comp (ref "U$4")
      (value "ELAST_10X10")
      (footprint "eagle-import:ELAST_PAD_SQUARE_10MM_4X4WIDE")
      (libsource (lib "eagle-import") (part "ELAST_10X10"))
    )
    (comp (ref "U$5")
      (value "ELAST_10X10")
      (footprint "eagle-import:ELAST_PAD_SQUARE_10MM_4X4WIDE")
      (libsource (lib "eagle-import") (part "ELAST_10X10"))
    )
    (comp (ref "U$6")
      (value "ELAST_10X10")
      (footprint "eagle-import:ELAST_PAD_SQUARE_10MM_4X4WIDE")
      (libsource (lib "eagle-import") (part "ELAST_10X10"))
    )
    (comp (ref "U$7")
      (value "ELAST_10X10")
      (footprint "eagle-import:ELAST_PAD_SQUARE_10MM_4X4WIDE")
      (libsource (lib "eagle-import") (part "ELAST_10X10"))
    )
    (comp (ref "U$8")
      (value "ELAST_10X10")
      (footprint "eagle-import:ELAST_PAD_SQUARE_10MM_4X4WIDE")
      (libsource (lib "eagle-import") (part "ELAST_10X10"))
    )
    (comp (ref "U$9")
      (value "ELAST_10X10")
      (footprint "eagle-import:ELAST_PAD_SQUARE_10MM_4X4WIDE")
      (libsource (lib "eagle-import") (part "ELAST_10X10"))
    )
    (comp (ref "U$10")
      (value "ELAST_10X10")
      (footprint "eagle-import:ELAST_PAD_SQUARE_10MM_4X4WIDE")
      (libsource (lib "eagle-import") (part "ELAST_10X10"))
    )
    (comp (ref "U$11")
      (value "ELAST_10X10")
      (footprint "eagle-import:ELAST_PAD_SQUARE_10MM_4X4WIDE")
      (libsource (lib "eagle-import") (part "ELAST_10X10"))
    )
    (comp (ref "U$12")
      (value "ELAST_10X10")
      (footprint "eagle-import:ELAST_PAD_SQUARE_10MM_4X4WIDE")
      (libsource (lib "eagle-import") (part "ELAST_10X10"))
    )
    (comp (ref "U$14")
      (value "ELAST_10X10")
      (footprint "eagle-import:ELAST_PAD_SQUARE_10MM_4X4WIDE")
      (libsource (lib "eagle-import") (part "ELAST_10X10"))
    )
    (comp (ref "U$19")
      (value "ELAST_10X10")
      (footprint "eagle-import:ELAST_PAD_SQUARE_10MM_4X4WIDE")
      (libsource (lib "eagle-import") (part "ELAST_10X10"))
    )
    (comp (ref "U$20")
      (value "ELAST_10X10")
      (footprint "eagle-import:ELAST_PAD_SQUARE_10MM_4X4WIDE")
      (libsource (lib "eagle-import") (part "ELAST_10X10"))
    )
    (comp (ref "U$23")
      (value "ELAST_10X10")
      (footprint "eagle-import:ELAST_PAD_SQUARE_10MM_4X4WIDE")
      (libsource (lib "eagle-import") (part "ELAST_10X10"))
    )
    (comp (ref "U$24")
      (value "ELAST_10X10")
      (footprint "eagle-import:ELAST_PAD_SQUARE_10MM_4X4WIDE")
      (libsource (lib "eagle-import") (part "ELAST_10X10"))
    )
    (comp (ref "U$25")
      (value "ELAST_10X10")
      (footprint "eagle-import:ELAST_PAD_SQUARE_10MM_4X4WIDE")
      (libsource (lib "eagle-import") (part "ELAST_10X10"))
    )
    (comp (ref "U$26")
      (value "ELAST_10X10")
      (footprint "eagle-import:ELAST_PAD_SQUARE_10MM_4X4WIDE")
      (libsource (lib "eagle-import") (part "ELAST_10X10"))
    )
    (comp (ref "U$27")
      (value "ELAST_10X10")
      (footprint "eagle-import:ELAST_PAD_SQUARE_10MM_4X4WIDE")
      (libsource (lib "eagle-import") (part "ELAST_10X10"))
    )
    (comp (ref "U$28")
      (value "ELAST_10X10")
      (footprint "eagle-import:ELAST_PAD_SQUARE_10MM_4X4WIDE")
      (libsource (lib "eagle-import") (part "ELAST_10X10"))
    )
    (comp (ref "U$29")
      (value "ELAST_10X10")
      (footprint "eagle-import:ELAST_PAD_SQUARE_10MM_4X4WIDE")
      (libsource (lib "eagle-import") (part "ELAST_10X10"))
    )
    (comp (ref "U$30")
      (value "ELAST_10X10")
      (footprint "eagle-import:ELAST_PAD_SQUARE_10MM_4X4WIDE")
      (libsource (lib "eagle-import") (part "ELAST_10X10"))
    )
    (comp (ref "U$31")
      (value "ELAST_10X10")
      (footprint "eagle-import:ELAST_PAD_SQUARE_10MM_4X4WIDE")
      (libsource (lib "eagle-import") (part "ELAST_10X10"))
    )
    (comp (ref "U$32")
      (value "ELAST_10X10")
      (footprint "eagle-import:ELAST_PAD_SQUARE_10MM_4X4WIDE")
      (libsource (lib "eagle-import") (part "ELAST_10X10"))
    )
    (comp (ref "U$33")
      (value "ELAST_10X10")
      (footprint "eagle-import:ELAST_PAD_SQUARE_10MM_4X4WIDE")
      (libsource (lib "eagle-import") (part "ELAST_10X10"))
    )
    (comp (ref "U$34")
      (value "ELAST_10X10")
      (footprint "eagle-import:ELAST_PAD_SQUARE_10MM_4X4WIDE")
      (libsource (lib "eagle-import") (part "ELAST_10X10"))
    )
    (comp (ref "U$35")
      (value "ELAST_10X10")
      (footprint "eagle-import:ELAST_PAD_SQUARE_10MM_4X4WIDE")
      (libsource (lib "eagle-import") (part "ELAST_10X10"))
    )
    (comp (ref "U$36")
      (value "ELAST_10X10")
      (footprint "eagle-import:ELAST_PAD_SQUARE_10MM_4X4WIDE")
      (libsource (lib "eagle-import") (part "ELAST_10X10"))
    )
    (comp (ref "U$37")
      (value "ELAST_10X10")
      (footprint "eagle-import:ELAST_PAD_SQUARE_10MM_4X4WIDE")
      (libsource (lib "eagle-import") (part "ELAST_10X10"))
    )
    (comp (ref "U$38")
      (value "ELAST_10X10")
      (footprint "eagle-import:ELAST_PAD_SQUARE_10MM_4X4WIDE")
      (libsource (lib "eagle-import") (part "ELAST_10X10"))
    )
    (comp (ref "U$39")
      (value "ELAST_10X10")
      (footprint "eagle-import:ELAST_PAD_SQUARE_10MM_4X4WIDE")
      (libsource (lib "eagle-import") (part "ELAST_10X10"))
    )
    (comp (ref "U$40")
      (value "ELAST_10X10")
      (footprint "eagle-import:ELAST_PAD_SQUARE_10MM_4X4WIDE")
      (libsource (lib "eagle-import") (part "ELAST_10X10"))
    )
    (comp (ref "U$41")
      (value "ELAST_10X10")
      (footprint "eagle-import:ELAST_PAD_SQUARE_10MM_4X4WIDE")
      (libsource (lib "eagle-import") (part "ELAST_10X10"))
    )
    (comp (ref "U$42")
      (value "ELAST_10X10")
      (footprint "eagle-import:ELAST_PAD_SQUARE_10MM_4X4WIDE")
      (libsource (lib "eagle-import") (part "ELAST_10X10"))
    )
    (comp (ref "U$43")
      (value "ELAST_10X10")
      (footprint "eagle-import:ELAST_PAD_SQUARE_10MM_4X4WIDE")
      (libsource (lib "eagle-import") (part "ELAST_10X10"))
    )
    (comp (ref "U$44")
      (value "ELAST_10X10")
      (footprint "eagle-import:ELAST_PAD_SQUARE_10MM_4X4WIDE")
      (libsource (lib "eagle-import") (part "ELAST_10X10"))
    )
    (comp (ref "U$45")
      (value "ELAST_10X10")
      (footprint "eagle-import:ELAST_PAD_SQUARE_10MM_4X4WIDE")
      (libsource (lib "eagle-import") (part "ELAST_10X10"))
    )
    (comp (ref "U$46")
      (value "ELAST_10X10")
      (footprint "eagle-import:ELAST_PAD_SQUARE_10MM_4X4WIDE")
      (libsource (lib "eagle-import") (part "ELAST_10X10"))
    )
    (comp (ref "U$47")
      (value "ELAST_10X10")
      (footprint "eagle-import:ELAST_PAD_SQUARE_10MM_4X4WIDE")
      (libsource (lib "eagle-import") (part "ELAST_10X10"))
    )
    (comp (ref "U$49")
      (value "ELAST_10X10")
      (footprint "eagle-import:ELAST_PAD_SQUARE_10MM_4X4WIDE")
      (libsource (lib "eagle-import") (part "ELAST_10X10"))
    )
    (comp (ref "U$54")
      (value "ELAST_10X10")
      (footprint "eagle-import:ELAST_PAD_SQUARE_10MM_4X4WIDE")
      (libsource (lib "eagle-import") (part "ELAST_10X10"))
    )
    (comp (ref "U$58")
      (value "ELAST_10X10")
      (footprint "eagle-import:ELAST_PAD_SQUARE_10MM_4X4WIDE")
      (libsource (lib "eagle-import") (part "ELAST_10X10"))
    )
    (comp (ref "U$59")
      (value "ELAST_10X10")
      (footprint "eagle-import:ELAST_PAD_SQUARE_10MM_4X4WIDE")
      (libsource (lib "eagle-import") (part "ELAST_10X10"))
    )
    (comp (ref "U$61")
      (value "ELAST_10X10")
      (footprint "eagle-import:ELAST_PAD_SQUARE_10MM_4X4WIDE")
      (libsource (lib "eagle-import") (part "ELAST_10X10"))
    )
    (comp (ref "U$67")
      (value "ELAST_10X10")
      (footprint "eagle-import:ELAST_PAD_SQUARE_10MM_4X4WIDE")
      (libsource (lib "eagle-import") (part "ELAST_10X10"))
    )
    (comp (ref "U$68")
      (value "ELAST_10X10")
      (footprint "eagle-import:ELAST_PAD_SQUARE_10MM_4X4WIDE")
      (libsource (lib "eagle-import") (part "ELAST_10X10"))
    )
    (comp (ref "U$69")
      (value "ELAST_10X10")
      (footprint "eagle-import:ELAST_PAD_SQUARE_10MM_4X4WIDE")
      (libsource (lib "eagle-import") (part "ELAST_10X10"))
    )
    (comp (ref "U$70")
      (value "ELAST_10X10")
      (footprint "eagle-import:ELAST_PAD_SQUARE_10MM_4X4WIDE")
      (libsource (lib "eagle-import") (part "ELAST_10X10"))
    )
    (comp (ref "U$71")
      (value "ELAST_10X10")
      (footprint "eagle-import:ELAST_PAD_SQUARE_10MM_4X4WIDE")
      (libsource (lib "eagle-import") (part "ELAST_10X10"))
    )
    (comp (ref "U$72")
      (value "ELAST_10X10")
      (footprint "eagle-import:ELAST_PAD_SQUARE_10MM_4X4WIDE")
      (libsource (lib "eagle-import") (part "ELAST_10X10"))
    )
    (comp (ref "U$73")
      (value "ELAST_10X10")
      (footprint "eagle-import:ELAST_PAD_SQUARE_10MM_4X4WIDE")
      (libsource (lib "eagle-import") (part "ELAST_10X10"))
    )
    (comp (ref "U$74")
      (value "ELAST_10X10")
      (footprint "eagle-import:ELAST_PAD_SQUARE_10MM_4X4WIDE")
      (libsource (lib "eagle-import") (part "ELAST_10X10"))
    )
    (comp (ref "U$75")
      (value "ELAST_10X10")
      (footprint "eagle-import:ELAST_PAD_SQUARE_10MM_4X4WIDE")
      (libsource (lib "eagle-import") (part "ELAST_10X10"))
    )
    (comp (ref "U$76")
      (value "ELAST_10X10")
      (footprint "eagle-import:ELAST_PAD_SQUARE_10MM_4X4WIDE")
      (libsource (lib "eagle-import") (part "ELAST_10X10"))
    )
    (comp (ref "U$77")
      (value "ELAST_10X10")
      (footprint "eagle-import:ELAST_PAD_SQUARE_10MM_4X4WIDE")
      (libsource (lib "eagle-import") (part "ELAST_10X10"))
    )
    (comp (ref "U$80")
      (value "ELAST_10X10")
      (footprint "eagle-import:ELAST_PAD_SQUARE_10MM_4X4WIDE")
      (libsource (lib "eagle-import") (part "ELAST_10X10"))
    )
  )
  (nets
    (net (code "1") (name "3.3V") (class "Default")
      (node (ref "C10") (pin "1") (pinfunction "1_1") (pintype "passive"))
      (node (ref "C11") (pin "1") (pinfunction "1_1") (pintype "passive"))
      (node (ref "C12") (pin "1") (pinfunction "1_1") (pintype "passive"))
      (node (ref "C14") (pin "1") (pinfunction "1_1") (pintype "passive"))
      (node (ref "IC4") (pin "17") (pinfunction "VDDIO_17") (pintype "power_in"))
      (node (ref "IC4") (pin "36") (pinfunction "VDDIO_36") (pintype "power_in"))
      (node (ref "IC4") (pin "44") (pinfunction "VDDIO_44") (pintype "power_in"))
      (node (ref "L2") (pin "3") (pinfunction "VDD_3") (pintype "power_in"))
      (node (ref "R11") (pin "2") (pinfunction "2_2") (pintype "passive"))
      (node (ref "R2") (pin "5") (pinfunction "2_5") (pintype "passive"))
      (node (ref "R2") (pin "6") (pinfunction "2_6") (pintype "passive"))
      (node (ref "R2") (pin "7") (pinfunction "2_7") (pintype "passive"))
      (node (ref "R2") (pin "8") (pinfunction "2_8") (pintype "passive"))
      (node (ref "U1") (pin "5") (pinfunction "OUT_5") (pintype "power_in"))
    )
    (net (code "2") (name "AVDD") (class "Default")
      (node (ref "IC4") (pin "6") (pinfunction "VDDA_6") (pintype "power_in"))
    )
    (net (code "3") (name "COL0") (class "Default")
      (node (ref "IC4") (pin "1") (pinfunction "PA00/EINT0/SERCOM1.0_1") (pintype "bidirectional"))
      (node (ref "TP12") (pin "P$1") (pinfunction "P$1_P$1") (pintype "bidirectional"))
      (node (ref "U$1") (pin "P$1") (pinfunction "P$1_P$1") (pintype "bidirectional"))
      (node (ref "U$12") (pin "P$1") (pinfunction "P$1_P$1") (pintype "bidirectional"))
      (node (ref "U$26") (pin "P$1") (pinfunction "P$1_P$1") (pintype "bidirectional"))
      (node (ref "U$30") (pin "P$1") (pinfunction "P$1_P$1") (pintype "bidirectional"))
      (node (ref "U$4") (pin "P$1") (pinfunction "P$1_P$1") (pintype "bidirectional"))
      (node (ref "U$54") (pin "P$1") (pinfunction "P$1_P$1") (pintype "bidirectional"))
      (node (ref "U$8") (pin "P$1") (pinfunction "P$1_P$1") (pintype "bidirectional"))
    )
    (net (code "4") (name "COL1") (class "Default")
      (node (ref "IC4") (pin "2") (pinfunction "PA01/EINT1/SERCOM1.1_2") (pintype "bidirectional"))
      (node (ref "TP13") (pin "P$1") (pinfunction "P$1_P$1") (pintype "bidirectional"))
      (node (ref "U$2") (pin "P$1") (pinfunction "P$1_P$1") (pintype "bidirectional"))
      (node (ref "U$23") (pin "P$1") (pinfunction "P$1_P$1") (pintype "bidirectional"))
      (node (ref "U$27") (pin "P$1") (pinfunction "P$1_P$1") (pintype "bidirectional"))
      (node (ref "U$31") (pin "P$1") (pinfunction "P$1_P$1") (pintype "bidirectional"))
      (node (ref "U$5") (pin "P$1") (pinfunction "P$1_P$1") (pintype "bidirectional"))
      (node (ref "U$58") (pin "P$1") (pinfunction "P$1_P$1") (pintype "bidirectional"))
      (node (ref "U$9") (pin "P$1") (pinfunction "P$1_P$1") (pintype "bidirectional"))
    )
    (net (code "5") (name "COL2") (class "Default")
      (node (ref "IC4") (pin "3") (pinfunction "PA02/EINT2/AIN0/VOUT0_3") (pintype "bidirectional"))
      (node (ref "TP14") (pin "P$1") (pinfunction "P$1_P$1") (pintype "bidirectional"))
      (node (ref "U$10") (pin "P$1") (pinfunction "P$1_P$1") (pintype "bidirectional"))
      (node (ref "U$14") (pin "P$1") (pinfunction "P$1_P$1") (pintype "bidirectional"))
      (node (ref "U$25") (pin "P$1") (pinfunction "P$1_P$1") (pintype "bidirectional"))
      (node (ref "U$28") (pin "P$1") (pinfunction "P$1_P$1") (pintype "bidirectional"))
      (node (ref "U$32") (pin "P$1") (pinfunction "P$1_P$1") (pintype "bidirectional"))
      (node (ref "U$59") (pin "P$1") (pinfunction "P$1_P$1") (pintype "bidirectional"))
      (node (ref "U$6") (pin "P$1") (pinfunction "P$1_P$1") (pintype "bidirectional"))
    )
    (net (code "6") (name "COL3") (class "Default")
      (node (ref "IC4") (pin "4") (pinfunction "PA03/I3/VREFA/AIN1_4") (pintype "bidirectional"))
      (node (ref "TP15") (pin "P$1") (pinfunction "P$1_P$1") (pintype "bidirectional"))
      (node (ref "U$11") (pin "P$1") (pinfunction "P$1_P$1") (pintype "bidirectional"))
      (node (ref "U$20") (pin "P$1") (pinfunction "P$1_P$1") (pintype "bidirectional"))
      (node (ref "U$24") (pin "P$1") (pinfunction "P$1_P$1") (pintype "bidirectional"))
      (node (ref "U$29") (pin "P$1") (pinfunction "P$1_P$1") (pintype "bidirectional"))
      (node (ref "U$49") (pin "P$1") (pinfunction "P$1_P$1") (pintype "bidirectional"))
      (node (ref "U$61") (pin "P$1") (pinfunction "P$1_P$1") (pintype "bidirectional"))
      (node (ref "U$7") (pin "P$1") (pinfunction "P$1_P$1") (pintype "bidirectional"))
    )
    (net (code "7") (name "COL4") (class "Default")
      (node (ref "IC4") (pin "10") (pinfunction "PA05/I5/AIN5/VOUT1/SERCOM0.1_10") (pintype "bidirectional"))
      (node (ref "TP16") (pin "P$1") (pinfunction "P$1_P$1") (pintype "bidirectional"))
      (node (ref "U$19") (pin "P$1") (pinfunction "P$1_P$1") (pintype "bidirectional"))
      (node (ref "U$36") (pin "P$1") (pinfunction "P$1_P$1") (pintype "bidirectional"))
      (node (ref "U$40") (pin "P$1") (pinfunction "P$1_P$1") (pintype "bidirectional"))
      (node (ref "U$44") (pin "P$1") (pinfunction "P$1_P$1") (pintype "bidirectional"))
      (node (ref "U$67") (pin "P$1") (pinfunction "P$1_P$1") (pintype "bidirectional"))
      (node (ref "U$71") (pin "P$1") (pinfunction "P$1_P$1") (pintype "bidirectional"))
      (node (ref "U$75") (pin "P$1") (pinfunction "P$1_P$1") (pintype "bidirectional"))
    )
    (net (code "8") (name "COL5") (class "Default")
      (node (ref "IC4") (pin "11") (pinfunction "PA06/I6/VREFC/AIN6/SERCOM0.2_11") (pintype "bidirectional"))
      (node (ref "TP17") (pin "P$1") (pinfunction "P$1_P$1") (pintype "bidirectional"))
      (node (ref "U$33") (pin "P$1") (pinfunction "P$1_P$1") (pintype "bidirectional"))
      (node (ref "U$37") (pin "P$1") (pinfunction "P$1_P$1") (pintype "bidirectional"))
      (node (ref "U$41") (pin "P$1") (pinfunction "P$1_P$1") (pintype "bidirectional"))
      (node (ref "U$45") (pin "P$1") (pinfunction "P$1_P$1") (pintype "bidirectional"))
      (node (ref "U$68") (pin "P$1") (pinfunction "P$1_P$1") (pintype "bidirectional"))
      (node (ref "U$72") (pin "P$1") (pinfunction "P$1_P$1") (pintype "bidirectional"))
      (node (ref "U$76") (pin "P$1") (pinfunction "P$1_P$1") (pintype "bidirectional"))
    )
    (net (code "9") (name "COL6") (class "Default")
      (node (ref "IC4") (pin "12") (pinfunction "PA07/I7/AIN7/SERCOM0.3_12") (pintype "bidirectional"))
      (node (ref "TP18") (pin "P$1") (pinfunction "P$1_P$1") (pintype "bidirectional"))
      (node (ref "U$34") (pin "P$1") (pinfunction "P$1_P$1") (pintype "bidirectional"))
      (node (ref "U$38") (pin "P$1") (pinfunction "P$1_P$1") (pintype "bidirectional"))
      (node (ref "U$43") (pin "P$1") (pinfunction "P$1_P$1") (pintype "bidirectional"))
      (node (ref "U$46") (pin "P$1") (pinfunction "P$1_P$1") (pintype "bidirectional"))
      (node (ref "U$69") (pin "P$1") (pinfunction "P$1_P$1") (pintype "bidirectional"))
      (node (ref "U$73") (pin "P$1") (pinfunction "P$1_P$1") (pintype "bidirectional"))
      (node (ref "U$77") (pin "P$1") (pinfunction "P$1_P$1") (pintype "bidirectional"))
    )
    (net (code "10") (name "COL7") (class "Default")
      (node (ref "IC4") (pin "13") (pinfunction "PA08/I2C/AIN8/SERCOM0.0+2.1/I2SMCK_13") (pintype "bidirectional"))
      (node (ref "TP19") (pin "P$1") (pinfunction "P$1_P$1") (pintype "bidirectional"))
      (node (ref "U$35") (pin "P$1") (pinfunction "P$1_P$1") (pintype "bidirectional"))
      (node (ref "U$39") (pin "P$1") (pinfunction "P$1_P$1") (pintype "bidirectional"))
      (node (ref "U$42") (pin "P$1") (pinfunction "P$1_P$1") (pintype "bidirectional"))
      (node (ref "U$47") (pin "P$1") (pinfunction "P$1_P$1") (pintype "bidirectional"))
      (node (ref "U$70") (pin "P$1") (pinfunction "P$1_P$1") (pintype "bidirectional"))
      (node (ref "U$74") (pin "P$1") (pinfunction "P$1_P$1") (pintype "bidirectional"))
      (node (ref "U$80") (pin "P$1") (pinfunction "P$1_P$1") (pintype "bidirectional"))
    )
    (net (code "11") (name "D+") (class "Default")
      (node (ref "IC4") (pin "34") (pinfunction "PA25/I9/SERCOM3+5.3/D+_34") (pintype "bidirectional"))
      (node (ref "X3") (pin "D+") (pinfunction "D+_D+") (pintype "bidirectional"))
    )
    (net (code "12") (name "D-") (class "Default")
      (node (ref "IC4") (pin "33") (pinfunction "PA24/I8/SERCOM3+5.2/D-_33") (pintype "bidirectional"))
      (node (ref "X3") (pin "D-") (pinfunction "D-_D-") (pintype "bidirectional"))
    )
    (net (code "13") (name "DOTSTAR_CLK") (class "Default")
      (node (ref "IC4") (pin "47") (pinfunction "PB02/I2/AIN14/SERCOM5.0_47") (pintype "bidirectional"))
      (node (ref "L2") (pin "5") (pinfunction "CKI_5") (pintype "input"))
    )
    (net (code "14") (name "DOTSTAR_DATA") (class "Default")
      (node (ref "IC4") (pin "48") (pinfunction "PB03/I3/AIN15/SERCOM5.1_48") (pintype "bidirectional"))
      (node (ref "L2") (pin "6") (pinfunction "DI_6") (pintype "input"))
    )
    (net (code "15") (name "GND") (class "Default")
      (node (ref "C1") (pin "1") (pinfunction "1_1") (pintype "passive"))
      (node (ref "C10") (pin "2") (pinfunction "2_2") (pintype "passive"))
      (node (ref "C11") (pin "2") (pinfunction "2_2") (pintype "passive"))
      (node (ref "C12") (pin "2") (pinfunction "2_2") (pintype "passive"))
      (node (ref "C13") (pin "2") (pinfunction "2_2") (pintype "passive"))
      (node (ref "C14") (pin "2") (pinfunction "2_2") (pintype "passive"))
      (node (ref "C15") (pin "1") (pinfunction "1_1") (pintype "passive"))
      (node (ref "C2") (pin "1") (pinfunction "1_1") (pintype "passive"))
      (node (ref "C3") (pin "1") (pinfunction "1_1") (pintype "passive"))
      (node (ref "C4") (pin "1") (pinfunction "1_1") (pintype "passive"))
      (node (ref "C5") (pin "1") (pinfunction "1_1") (pintype "passive"))
      (node (ref "C6") (pin "1") (pinfunction "1_1") (pintype "passive"))
      (node (ref "C9") (pin "2") (pinfunction "2_2") (pintype "passive"))
      (node (ref "IC2") (pin "1") (pinfunction "OE_1") (pintype "input"))
      (node (ref "IC2") (pin "3") (pinfunction "GND_3") (pintype "power_in"))
      (node (ref "IC4") (pin "18") (pinfunction "GND_18") (pintype "power_in"))
      (node (ref "IC4") (pin "35") (pinfunction "GND_35") (pintype "power_in"))
      (node (ref "IC4") (pin "42") (pinfunction "GND_42") (pintype "power_in"))
      (node (ref "IC4") (pin "THERMAL") (pinfunction "TP_THERMAL") (pintype "power_in"))
      (node (ref "J2") (pin "2") (pinfunction "2_2") (pintype "bidirectional"))
      (node (ref "JP3") (pin "3") (pinfunction "3_3") (pintype "passive"))
      (node (ref "JP4") (pin "3") (pinfunction "3_3") (pintype "passive"))
      (node (ref "L2") (pin "4") (pinfunction "GND_4") (pintype "power_in"))
      (node (ref "LED1") (pin "4") (pinfunction "GND_4") (pintype "power_in"))
      (node (ref "LED10") (pin "4") (pinfunction "GND_4") (pintype "power_in"))
      (node (ref "LED11") (pin "4") (pinfunction "GND_4") (pintype "power_in"))
      (node (ref "LED12") (pin "4") (pinfunction "GND_4") (pintype "power_in"))
      (node (ref "LED13") (pin "4") (pinfunction "GND_4") (pintype "power_in"))
      (node (ref "LED14") (pin "4") (pinfunction "GND_4") (pintype "power_in"))
      (node (ref "LED15") (pin "4") (pinfunction "GND_4") (pintype "power_in"))
      (node (ref "LED16") (pin "4") (pinfunction "GND_4") (pintype "power_in"))
      (node (ref "LED17") (pin "4") (pinfunction "GND_4") (pintype "power_in"))
      (node (ref "LED18") (pin "4") (pinfunction "GND_4") (pintype "power_in"))
      (node (ref "LED19") (pin "4") (pinfunction "GND_4") (pintype "power_in"))
      (node (ref "LED2") (pin "4") (pinfunction "GND_4") (pintype "power_in"))
      (node (ref "LED20") (pin "4") (pinfunction "GND_4") (pintype "power_in"))
      (node (ref "LED21") (pin "4") (pinfunction "GND_4") (pintype "power_in"))
      (node (ref "LED22") (pin "4") (pinfunction "GND_4") (pintype "power_in"))
      (node (ref "LED23") (pin "4") (pinfunction "GND_4") (pintype "power_in"))
      (node (ref "LED24") (pin "4") (pinfunction "GND_4") (pintype "power_in"))
      (node (ref "LED25") (pin "4") (pinfunction "GND_4") (pintype "power_in"))
      (node (ref "LED26") (pin "4") (pinfunction "GND_4") (pintype "power_in"))
      (node (ref "LED27") (pin "4") (pinfunction "GND_4") (pintype "power_in"))
      (node (ref "LED28") (pin "4") (pinfunction "GND_4") (pintype "power_in"))
      (node (ref "LED29") (pin "4") (pinfunction "GND_4") (pintype "power_in"))
      (node (ref "LED3") (pin "4") (pinfunction "GND_4") (pintype "power_in"))
      (node (ref "LED30") (pin "4") (pinfunction "GND_4") (pintype "power_in"))
      (node (ref "LED31") (pin "4") (pinfunction "GND_4") (pintype "power_in"))
      (node (ref "LED32") (pin "4") (pinfunction "GND_4") (pintype "power_in"))
      (node (ref "LED33") (pin "4") (pinfunction "GND_4") (pintype "power_in"))
      (node (ref "LED34") (pin "4") (pinfunction "GND_4") (pintype "power_in"))
      (node (ref "LED35") (pin "4") (pinfunction "GND_4") (pintype "power_in"))
      (node (ref "LED36") (pin "4") (pinfunction "GND_4") (pintype "power_in"))
      (node (ref "LED37") (pin "4") (pinfunction "GND_4") (pintype "power_in"))
      (node (ref "LED38") (pin "4") (pinfunction "GND_4") (pintype "power_in"))
      (node (ref "LED39") (pin "4") (pinfunction "GND_4") (pintype "power_in"))
      (node (ref "LED4") (pin "4") (pinfunction "GND_4") (pintype "power_in"))
      (node (ref "LED40") (pin "4") (pinfunction "GND_4") (pintype "power_in"))
      (node (ref "LED41") (pin "4") (pinfunction "GND_4") (pintype "power_in"))
      (node (ref "LED42") (pin "4") (pinfunction "GND_4") (pintype "power_in"))
      (node (ref "LED43") (pin "4") (pinfunction "GND_4") (pintype "power_in"))
      (node (ref "LED44") (pin "4") (pinfunction "GND_4") (pintype "power_in"))
      (node (ref "LED45") (pin "4") (pinfunction "GND_4") (pintype "power_in"))
      (node (ref "LED46") (pin "4") (pinfunction "GND_4") (pintype "power_in"))
      (node (ref "LED47") (pin "4") (pinfunction "GND_4") (pintype "power_in"))
      (node (ref "LED48") (pin "4") (pinfunction "GND_4") (pintype "power_in"))
      (node (ref "LED49") (pin "4") (pinfunction "GND_4") (pintype "power_in"))
      (node (ref "LED5") (pin "4") (pinfunction "GND_4") (pintype "power_in"))
      (node (ref "LED50") (pin "4") (pinfunction "GND_4") (pintype "power_in"))
      (node (ref "LED51") (pin "4") (pinfunction "GND_4") (pintype "power_in"))
      (node (ref "LED52") (pin "4") (pinfunction "GND_4") (pintype "power_in"))
      (node (ref "LED53") (pin "4") (pinfunction "GND_4") (pintype "power_in"))
      (node (ref "LED54") (pin "4") (pinfunction "GND_4") (pintype "power_in"))
      (node (ref "LED55") (pin "4") (pinfunction "GND_4") (pintype "power_in"))
      (node (ref "LED56") (pin "4") (pinfunction "GND_4") (pintype "power_in"))
      (node (ref "LED6") (pin "4") (pinfunction "GND_4") (pintype "power_in"))
      (node (ref "LED7") (pin "4") (pinfunction "GND_4") (pintype "power_in"))
      (node (ref "LED8") (pin "4") (pinfunction "GND_4") (pintype "power_in"))
      (node (ref "LED9") (pin "4") (pinfunction "GND_4") (pintype "power_in"))
      (node (ref "SW1") (pin "2") (pinfunction "S_2") (pintype "passive"))
      (node (ref "SW1") (pin "4") (pinfunction "S1_4") (pintype "passive"))
      (node (ref "U1") (pin "2") (pinfunction "GND_2") (pintype "power_in"))
      (node (ref "X3") (pin "BASE@1") (pinfunction "GND_BASE@1") (pintype "power_in"))
      (node (ref "X3") (pin "BASE@2") (pinfunction "GND_BASE@2") (pintype "power_in"))
      (node (ref "X3") (pin "GND") (pinfunction "GND_GND") (pintype "power_in"))
      (node (ref "X3") (pin "SPRT@1") (pinfunction "GND_SPRT@1") (pintype "power_in"))
      (node (ref "X3") (pin "SPRT@2") (pinfunction "GND_SPRT@2") (pintype "power_in"))
      (node (ref "X3") (pin "SPRT@3") (pinfunction "GND_SPRT@3") (pintype "power_in"))
      (node (ref "X3") (pin "SPRT@4") (pinfunction "GND_SPRT@4") (pintype "power_in"))
    )
    (net (code "16") (name "INT") (class "Default")
      (node (ref "IC4") (pin "9") (pinfunction "PA04/I4/VREFB/AIN4/SERCOM0.0_9") (pintype "bidirectional"))
      (node (ref "JP3") (pin "1") (pinfunction "1_1") (pintype "passive"))
      (node (ref "JP4") (pin "1") (pinfunction "1_1") (pintype "passive"))
      (node (ref "R2") (pin "2") (pinfunction "1_2") (pintype "passive"))
    )
    (net (code "17") (name "LEVELSHIFT_3V") (class "Default")
      (node (ref "IC2") (pin "2") (pinfunction "I_2") (pintype "input"))
      (node (ref "IC4") (pin "39") (pinfunction "PA27/I11_39") (pintype "bidirectional"))
    )
    (net (code "18") (name "LEVELSHIFT_5V") (class "Default")
      (node (ref "IC2") (pin "4") (pinfunction "O_4") (pintype "tri_state"))
      (node (ref "LED1") (pin "1") (pinfunction "DI_1") (pintype "input"))
      (node (ref "R3") (pin "1") (pinfunction "1_1") (pintype "passive"))
    )
    (net (code "19") (name "MIDIOUT") (class "Default")
      (node (ref "IC4") (pin "32") (pinfunction "PA23/I2C/I7/SERCOM3.1+5.0/SOF/I2SFS1_32") (pintype "bidirectional"))
      (node (ref "R4") (pin "1") (pinfunction "1_1") (pintype "passive"))
    )
    (net (code "20") (name "Net-(D1-PadC)") (class "Default")
      (node (ref "D1") (pin "C") (pinfunction "C_C") (pintype "passive"))
      (node (ref "TP21") (pin "P$1") (pinfunction "P$1_P$1") (pintype "bidirectional"))
      (node (ref "U$5") (pin "P$2") (pinfunction "P$2_P$2") (pintype "bidirectional"))
    )
    (net (code "21") (name "Net-(D2-PadC)") (class "Default")
      (node (ref "D2") (pin "C") (pinfunction "C_C") (pintype "passive"))
      (node (ref "TP22") (pin "P$1") (pinfunction "P$1_P$1") (pintype "bidirectional"))
      (node (ref "U$6") (pin "P$2") (pinfunction "P$2_P$2") (pintype "bidirectional"))
    )
    (net (code "22") (name "Net-(D3-PadC)") (class "Default")
      (node (ref "D3") (pin "C") (pinfunction "C_C") (pintype "passive"))
      (node (ref "TP23") (pin "P$1") (pinfunction "P$1_P$1") (pintype "bidirectional"))
      (node (ref "U$7") (pin "P$2") (pinfunction "P$2_P$2") (pintype "bidirectional"))
    )
    (net (code "23") (name "Net-(D4-PadC)") (class "Default")
      (node (ref "D4") (pin "C") (pinfunction "C_C") (pintype "passive"))
      (node (ref "TP8") (pin "P$1") (pinfunction "P$1_P$1") (pintype "bidirectional"))
      (node (ref "U$8") (pin "P$2") (pinfunction "P$2_P$2") (pintype "bidirectional"))
    )
    (net (code "24") (name "Net-(D5-PadC)") (class "Default")
      (node (ref "D5") (pin "C") (pinfunction "C_C") (pintype "passive"))
      (node (ref "TP24") (pin "P$1") (pinfunction "P$1_P$1") (pintype "bidirectional"))
      (node (ref "U$9") (pin "P$2") (pinfunction "P$2_P$2") (pintype "bidirectional"))
    )
    (net (code "25") (name "Net-(D6-PadC)") (class "Default")
      (node (ref "D6") (pin "C") (pinfunction "C_C") (pintype "passive"))
      (node (ref "TP34") (pin "P$1") (pinfunction "P$1_P$1") (pintype "bidirectional"))
      (node (ref "U$10") (pin "P$2") (pinfunction "P$2_P$2") (pintype "bidirectional"))
    )
    (net (code "26") (name "Net-(D7-PadC)") (class "Default")
      (node (ref "D7") (pin "C") (pinfunction "C_C") (pintype "passive"))
      (node (ref "TP25") (pin "P$1") (pinfunction "P$1_P$1") (pintype "bidirectional"))
      (node (ref "U$11") (pin "P$2") (pinfunction "P$2_P$2") (pintype "bidirectional"))
    )
    (net (code "27") (name "Net-(D8-PadC)") (class "Default")
      (node (ref "D8") (pin "C") (pinfunction "C_C") (pintype "passive"))
      (node (ref "TP33") (pin "P$1") (pinfunction "P$1_P$1") (pintype "bidirectional"))
      (node (ref "U$12") (pin "P$2") (pinfunction "P$2_P$2") (pintype "bidirectional"))
    )
    (net (code "28") (name "Net-(D9-PadC)") (class "Default")
      (node (ref "D9") (pin "C") (pinfunction "C_C") (pintype "passive"))
      (node (ref "TP20") (pin "P$1") (pinfunction "P$1_P$1") (pintype "bidirectional"))
      (node (ref "U$4") (pin "P$2") (pinfunction "P$2_P$2") (pintype "bidirectional"))
    )
    (net (code "29") (name "Net-(D10-PadC)") (class "Default")
      (node (ref "D10") (pin "C") (pinfunction "C_C") (pintype "passive"))
      (node (ref "TP26") (pin "P$1") (pinfunction "P$1_P$1") (pintype "bidirectional"))
      (node (ref "U$23") (pin "P$2") (pinfunction "P$2_P$2") (pintype "bidirectional"))
    )
    (net (code "30") (name "Net-(D11-PadC)") (class "Default")
      (node (ref "D11") (pin "C") (pinfunction "C_C") (pintype "passive"))
      (node (ref "TP32") (pin "P$1") (pinfunction "P$1_P$1") (pintype "bidirectional"))
      (node (ref "U$25") (pin "P$2") (pinfunction "P$2_P$2") (pintype "bidirectional"))
    )
    (net (code "31") (name "Net-(D12-PadC)") (class "Default")
      (node (ref "D12") (pin "C") (pinfunction "C_C") (pintype "passive"))
      (node (ref "TP27") (pin "P$1") (pinfunction "P$1_P$1") (pintype "bidirectional"))
      (node (ref "U$24") (pin "P$2") (pinfunction "P$2_P$2") (pintype "bidirectional"))
    )
    (net (code "32") (name "Net-(D13-PadC)") (class "Default")
      (node (ref "D13") (pin "C") (pinfunction "C_C") (pintype "passive"))
      (node (ref "TP31") (pin "P$1") (pinfunction "P$1_P$1") (pintype "bidirectional"))
      (node (ref "U$26") (pin "P$2") (pinfunction "P$2_P$2") (pintype "bidirectional"))
    )
    (net (code "33") (name "Net-(D14-PadC)") (class "Default")
      (node (ref "D14") (pin "C") (pinfunction "C_C") (pintype "passive"))
      (node (ref "TP28") (pin "P$1") (pinfunction "P$1_P$1") (pintype "bidirectional"))
      (node (ref "U$27") (pin "P$2") (pinfunction "P$2_P$2") (pintype "bidirectional"))
    )
    (net (code "34") (name "Net-(D15-PadC)") (class "Default")
      (node (ref "D15") (pin "C") (pinfunction "C_C") (pintype "passive"))
      (node (ref "TP30") (pin "P$1") (pinfunction "P$1_P$1") (pintype "bidirectional"))
      (node (ref "U$28") (pin "P$2") (pinfunction "P$2_P$2") (pintype "bidirectional"))
    )
    (net (code "35") (name "Net-(D16-PadC)") (class "Default")
      (node (ref "D16") (pin "C") (pinfunction "C_C") (pintype "passive"))
      (node (ref "TP29") (pin "P$1") (pinfunction "P$1_P$1") (pintype "bidirectional"))
      (node (ref "U$29") (pin "P$2") (pinfunction "P$2_P$2") (pintype "bidirectional"))
    )
    (net (code "36") (name "Net-(D17-PadC)") (class "Default")
      (node (ref "D17") (pin "C") (pinfunction "C_C") (pintype "passive"))
      (node (ref "TP35") (pin "P$1") (pinfunction "P$1_P$1") (pintype "bidirectional"))
      (node (ref "U$19") (pin "P$2") (pinfunction "P$2_P$2") (pintype "bidirectional"))
    )
    (net (code "37") (name "Net-(D18-PadC)") (class "Default")
      (node (ref "D18") (pin "C") (pinfunction "C_C") (pintype "passive"))
      (node (ref "TP36") (pin "P$1") (pinfunction "P$1_P$1") (pintype "bidirectional"))
      (node (ref "U$33") (pin "P$2") (pinfunction "P$2_P$2") (pintype "bidirectional"))
    )
    (net (code "38") (name "Net-(D19-PadC)") (class "Default")
      (node (ref "D19") (pin "C") (pinfunction "C_C") (pintype "passive"))
      (node (ref "TP38") (pin "P$1") (pinfunction "P$1_P$1") (pintype "bidirectional"))
      (node (ref "U$34") (pin "P$2") (pinfunction "P$2_P$2") (pintype "bidirectional"))
    )
    (net (code "39") (name "Net-(D20-PadC)") (class "Default")
      (node (ref "D20") (pin "C") (pinfunction "C_C") (pintype "passive"))
      (node (ref "TP37") (pin "P$1") (pinfunction "P$1_P$1") (pintype "bidirectional"))
      (node (ref "U$35") (pin "P$2") (pinfunction "P$2_P$2") (pintype "bidirectional"))
    )
    (net (code "40") (name "Net-(D21-PadC)") (class "Default")
      (node (ref "D21") (pin "C") (pinfunction "C_C") (pintype "passive"))
      (node (ref "TP39") (pin "P$1") (pinfunction "P$1_P$1") (pintype "bidirectional"))
      (node (ref "U$36") (pin "P$2") (pinfunction "P$2_P$2") (pintype "bidirectional"))
    )
    (net (code "41") (name "Net-(D22-PadC)") (class "Default")
      (node (ref "D22") (pin "C") (pinfunction "C_C") (pintype "passive"))
      (node (ref "TP40") (pin "P$1") (pinfunction "P$1_P$1") (pintype "bidirectional"))
      (node (ref "U$37") (pin "P$2") (pinfunction "P$2_P$2") (pintype "bidirectional"))
    )
    (net (code "42") (name "Net-(D23-PadC)") (class "Default")
      (node (ref "D23") (pin "C") (pinfunction "C_C") (pintype "passive"))
      (node (ref "TP42") (pin "P$1") (pinfunction "P$1_P$1") (pintype "bidirectional"))
      (node (ref "U$38") (pin "P$2") (pinfunction "P$2_P$2") (pintype "bidirectional"))
    )
    (net (code "43") (name "Net-(D24-PadC)") (class "Default")
      (node (ref "D24") (pin "C") (pinfunction "C_C") (pintype "passive"))
      (node (ref "TP41") (pin "P$1") (pinfunction "P$1_P$1") (pintype "bidirectional"))
      (node (ref "U$39") (pin "P$2") (pinfunction "P$2_P$2") (pintype "bidirectional"))
    )
    (net (code "44") (name "Net-(D25-PadC)") (class "Default")
      (node (ref "D25") (pin "C") (pinfunction "C_C") (pintype "passive"))
      (node (ref "TP43") (pin "P$1") (pinfunction "P$1_P$1") (pintype "bidirectional"))
      (node (ref "U$40") (pin "P$2") (pinfunction "P$2_P$2") (pintype "bidirectional"))
    )
    (net (code "45") (name "Net-(D26-PadC)") (class "Default")
      (node (ref "D26") (pin "C") (pinfunction "C_C") (pintype "passive"))
      (node (ref "TP44") (pin "P$1") (pinfunction "P$1_P$1") (pintype "bidirectional"))
      (node (ref "U$41") (pin "P$2") (pinfunction "P$2_P$2") (pintype "bidirectional"))
    )
    (net (code "46") (name "Net-(D27-PadC)") (class "Default")
      (node (ref "D27") (pin "C") (pinfunction "C_C") (pintype "passive"))
      (node (ref "TP46") (pin "P$1") (pinfunction "P$1_P$1") (pintype "bidirectional"))
      (node (ref "U$43") (pin "P$2") (pinfunction "P$2_P$2") (pintype "bidirectional"))
    )
    (net (code "47") (name "Net-(D28-PadC)") (class "Default")
      (node (ref "D28") (pin "C") (pinfunction "C_C") (pintype "passive"))
      (node (ref "TP45") (pin "P$1") (pinfunction "P$1_P$1") (pintype "bidirectional"))
      (node (ref "U$42") (pin "P$2") (pinfunction "P$2_P$2") (pintype "bidirectional"))
    )
    (net (code "48") (name "Net-(D29-PadC)") (class "Default")
      (node (ref "D29") (pin "C") (pinfunction "C_C") (pintype "passive"))
      (node (ref "TP47") (pin "P$1") (pinfunction "P$1_P$1") (pintype "bidirectional"))
      (node (ref "U$44") (pin "P$2") (pinfunction "P$2_P$2") (pintype "bidirectional"))
    )
    (net (code "49") (name "Net-(D30-PadC)") (class "Default")
      (node (ref "D30") (pin "C") (pinfunction "C_C") (pintype "passive"))
      (node (ref "TP49") (pin "P$1") (pinfunction "P$1_P$1") (pintype "bidirectional"))
      (node (ref "U$45") (pin "P$2") (pinfunction "P$2_P$2") (pintype "bidirectional"))
    )
    (net (code "50") (name "Net-(D31-PadC)") (class "Default")
      (node (ref "D31") (pin "C") (pinfunction "C_C") (pintype "passive"))
      (node (ref "TP48") (pin "P$1") (pinfunction "P$1_P$1") (pintype "bidirectional"))
      (node (ref "U$46") (pin "P$2") (pinfunction "P$2_P$2") (pintype "bidirectional"))
    )
    (net (code "51") (name "Net-(D32-PadC)") (class "Default")
      (node (ref "D32") (pin "C") (pinfunction "C_C") (pintype "passive"))
      (node (ref "TP50") (pin "P$1") (pinfunction "P$1_P$1") (pintype "bidirectional"))
      (node (ref "U$47") (pin "P$2") (pinfunction "P$2_P$2") (pintype "bidirectional"))
    )
    (net (code "52") (name "Net-(D33-PadC)") (class "Default")
      (node (ref "D33") (pin "C") (pinfunction "C_C") (pintype "passive"))
      (node (ref "TP9") (pin "P$1") (pinfunction "P$1_P$1") (pintype "bidirectional"))
      (node (ref "U$1") (pin "P$2") (pinfunction "P$2_P$2") (pintype "bidirectional"))
    )
    (net (code "53") (name "Net-(D35-PadC)") (class "Default")
      (node (ref "D35") (pin "C") (pinfunction "C_C") (pintype "passive"))
      (node (ref "TP5") (pin "P$1") (pinfunction "P$1_P$1") (pintype "bidirectional"))
      (node (ref "U$2") (pin "P$2") (pinfunction "P$2_P$2") (pintype "bidirectional"))
    )
    (net (code "54") (name "Net-(D36-PadC)") (class "Default")
      (node (ref "D36") (pin "C") (pinfunction "C_C") (pintype "passive"))
      (node (ref "TP7") (pin "P$1") (pinfunction "P$1_P$1") (pintype "bidirectional"))
      (node (ref "U$14") (pin "P$2") (pinfunction "P$2_P$2") (pintype "bidirectional"))
    )
    (net (code "55") (name "Net-(D37-PadC)") (class "Default")
      (node (ref "D37") (pin "C") (pinfunction "C_C") (pintype "passive"))
      (node (ref "TP6") (pin "P$1") (pinfunction "P$1_P$1") (pintype "bidirectional"))
      (node (ref "U$20") (pin "P$2") (pinfunction "P$2_P$2") (pintype "bidirectional"))
    )
    (net (code "56") (name "Net-(D38-PadC)") (class "Default")
      (node (ref "D38") (pin "C") (pinfunction "C_C") (pintype "passive"))
      (node (ref "TP52") (pin "P$1") (pinfunction "P$1_P$1") (pintype "bidirectional"))
      (node (ref "U$30") (pin "P$2") (pinfunction "P$2_P$2") (pintype "bidirectional"))
    )
    (net (code "57") (name "Net-(D39-PadC)") (class "Default")
      (node (ref "D39") (pin "C") (pinfunction "C_C") (pintype "passive"))
      (node (ref "TP10") (pin "P$1") (pinfunction "P$1_P$1") (pintype "bidirectional"))
      (node (ref "U$31") (pin "P$2") (pinfunction "P$2_P$2") (pintype "bidirectional"))
    )
    (net (code "58") (name "Net-(D40-PadC)") (class "Default")
      (node (ref "D40") (pin "C") (pinfunction "C_C") (pintype "passive"))
      (node (ref "TP51") (pin "P$1") (pinfunction "P$1_P$1") (pintype "bidirectional"))
      (node (ref "U$32") (pin "P$2") (pinfunction "P$2_P$2") (pintype "bidirectional"))
    )
    (net (code "59") (name "Net-(D41-PadC)") (class "Default")
      (node (ref "D41") (pin "C") (pinfunction "C_C") (pintype "passive"))
      (node (ref "TP11") (pin "P$1") (pinfunction "P$1_P$1") (pintype "bidirectional"))
      (node (ref "U$49") (pin "P$2") (pinfunction "P$2_P$2") (pintype "bidirectional"))
    )
    (net (code "60") (name "Net-(D42-PadC)") (class "Default")
      (node (ref "D42") (pin "C") (pinfunction "C_C") (pintype "passive"))
      (node (ref "TP56") (pin "P$1") (pinfunction "P$1_P$1") (pintype "bidirectional"))
      (node (ref "U$54") (pin "P$2") (pinfunction "P$2_P$2") (pintype "bidirectional"))
    )
    (net (code "61") (name "Net-(D43-PadC)") (class "Default")
      (node (ref "D43") (pin "C") (pinfunction "C_C") (pintype "passive"))
      (node (ref "TP53") (pin "P$1") (pinfunction "P$1_P$1") (pintype "bidirectional"))
      (node (ref "U$58") (pin "P$2") (pinfunction "P$2_P$2") (pintype "bidirectional"))
    )
    (net (code "62") (name "Net-(D44-PadC)") (class "Default")
      (node (ref "D44") (pin "C") (pinfunction "C_C") (pintype "passive"))
      (node (ref "TP55") (pin "P$1") (pinfunction "P$1_P$1") (pintype "bidirectional"))
      (node (ref "U$59") (pin "P$2") (pinfunction "P$2_P$2") (pintype "bidirectional"))
    )
    (net (code "63") (name "Net-(D45-PadC)") (class "Default")
      (node (ref "D45") (pin "C") (pinfunction "C_C") (pintype "passive"))
      (node (ref "TP54") (pin "P$1") (pinfunction "P$1_P$1") (pintype "bidirectional"))
      (node (ref "U$61") (pin "P$2") (pinfunction "P$2_P$2") (pintype "bidirectional"))
    )
    (net (code "64") (name "Net-(D46-PadC)") (class "Default")
      (node (ref "D46") (pin "C") (pinfunction "C_C") (pintype "passive"))
      (node (ref "TP60") (pin "P$1") (pinfunction "P$1_P$1") (pintype "bidirectional"))
      (node (ref "U$67") (pin "P$2") (pinfunction "P$2_P$2") (pintype "bidirectional"))
    )
    (net (code "65") (name "Net-(D47-PadC)") (class "Default")
      (node (ref "D47") (pin "C") (pinfunction "C_C") (pintype "passive"))
      (node (ref "TP57") (pin "P$1") (pinfunction "P$1_P$1") (pintype "bidirectional"))
      (node (ref "U$68") (pin "P$2") (pinfunction "P$2_P$2") (pintype "bidirectional"))
    )
    (net (code "66") (name "Net-(D48-PadC)") (class "Default")
      (node (ref "D48") (pin "C") (pinfunction "C_C") (pintype "passive"))
      (node (ref "TP59") (pin "P$1") (pinfunction "P$1_P$1") (pintype "bidirectional"))
      (node (ref "U$69") (pin "P$2") (pinfunction "P$2_P$2") (pintype "bidirectional"))
    )
    (net (code "67") (name "Net-(D49-PadC)") (class "Default")
      (node (ref "D49") (pin "C") (pinfunction "C_C") (pintype "passive"))
      (node (ref "TP58") (pin "P$1") (pinfunction "P$1_P$1") (pintype "bidirectional"))
      (node (ref "U$70") (pin "P$2") (pinfunction "P$2_P$2") (pintype "bidirectional"))
    )
    (net (code "68") (name "Net-(D50-PadC)") (class "Default")
      (node (ref "D50") (pin "C") (pinfunction "C_C") (pintype "passive"))
      (node (ref "TP64") (pin "P$1") (pinfunction "P$1_P$1") (pintype "bidirectional"))
      (node (ref "U$71") (pin "P$2") (pinfunction "P$2_P$2") (pintype "bidirectional"))
    )
    (net (code "69") (name "Net-(D51-PadC)") (class "Default")
      (node (ref "D51") (pin "C") (pinfunction "C_C") (pintype "passive"))
      (node (ref "TP61") (pin "P$1") (pinfunction "P$1_P$1") (pintype "bidirectional"))
      (node (ref "U$72") (pin "P$2") (pinfunction "P$2_P$2") (pintype "bidirectional"))
    )
    (net (code "70") (name "Net-(D52-PadC)") (class "Default")
      (node (ref "D52") (pin "C") (pinfunction "C_C") (pintype "passive"))
      (node (ref "TP63") (pin "P$1") (pinfunction "P$1_P$1") (pintype "bidirectional"))
      (node (ref "U$73") (pin "P$2") (pinfunction "P$2_P$2") (pintype "bidirectional"))
    )
    (net (code "71") (name "Net-(D53-PadC)") (class "Default")
      (node (ref "D53") (pin "C") (pinfunction "C_C") (pintype "passive"))
      (node (ref "TP62") (pin "P$1") (pinfunction "P$1_P$1") (pintype "bidirectional"))
      (node (ref "U$74") (pin "P$2") (pinfunction "P$2_P$2") (pintype "bidirectional"))
    )
    (net (code "72") (name "Net-(D54-PadC)") (class "Default")
      (node (ref "D54") (pin "C") (pinfunction "C_C") (pintype "passive"))
      (node (ref "TP68") (pin "P$1") (pinfunction "P$1_P$1") (pintype "bidirectional"))
      (node (ref "U$75") (pin "P$2") (pinfunction "P$2_P$2") (pintype "bidirectional"))
    )
    (net (code "73") (name "Net-(D55-PadC)") (class "Default")
      (node (ref "D55") (pin "C") (pinfunction "C_C") (pintype "passive"))
      (node (ref "TP65") (pin "P$1") (pinfunction "P$1_P$1") (pintype "bidirectional"))
      (node (ref "U$76") (pin "P$2") (pinfunction "P$2_P$2") (pintype "bidirectional"))
    )
    (net (code "74") (name "Net-(D56-PadC)") (class "Default")
      (node (ref "D56") (pin "C") (pinfunction "C_C") (pintype "passive"))
      (node (ref "TP67") (pin "P$1") (pinfunction "P$1_P$1") (pintype "bidirectional"))
      (node (ref "U$77") (pin "P$2") (pinfunction "P$2_P$2") (pintype "bidirectional"))
    )
    (net (code "75") (name "Net-(D57-PadC)") (class "Default")
      (node (ref "D57") (pin "C") (pinfunction "C_C") (pintype "passive"))
      (node (ref "TP66") (pin "P$1") (pinfunction "P$1_P$1") (pintype "bidirectional"))
      (node (ref "U$80") (pin "P$2") (pinfunction "P$2_P$2") (pintype "bidirectional"))
    )
    (net (code "76") (name "Net-(IC4A-VDDCORE)") (class "Default")
      (node (ref "C13") (pin "1") (pinfunction "1_1") (pintype "passive"))
      (node (ref "IC4") (pin "41") (pinfunction "VDDCORE_41") (pintype "power_in"))
    )
    (net (code "77") (name "Net-(J2-Pad4)") (class "Default")
      (node (ref "J2") (pin "4") (pinfunction "4_4") (pintype "bidirectional"))
      (node (ref "R3") (pin "2") (pinfunction "2_2") (pintype "passive"))
    )
    (net (code "78") (name "Net-(J2-Pad5)") (class "Default")
      (node (ref "J2") (pin "5") (pinfunction "5_5") (pintype "bidirectional"))
      (node (ref "R4") (pin "2") (pinfunction "2_2") (pintype "passive"))
    )
    (net (code "79") (name "Net-(LED1-DO)") (class "Default")
      (node (ref "LED1") (pin "3") (pinfunction "DO_3") (pintype "output"))
      (node (ref "LED2") (pin "1") (pinfunction "DI_1") (pintype "input"))
    )
    (net (code "80") (name "Net-(LED2-DO)") (class "Default")
      (node (ref "LED2") (pin "3") (pinfunction "DO_3") (pintype "output"))
      (node (ref "LED3") (pin "1") (pinfunction "DI_1") (pintype "input"))
    )
    (net (code "81") (name "Net-(LED3-DO)") (class "Default")
      (node (ref "LED3") (pin "3") (pinfunction "DO_3") (pintype "output"))
      (node (ref "LED4") (pin "1") (pinfunction "DI_1") (pintype "input"))
    )
    (net (code "82") (name "Net-(LED4-DO)") (class "Default")
      (node (ref "LED4") (pin "3") (pinfunction "DO_3") (pintype "output"))
      (node (ref "LED5") (pin "1") (pinfunction "DI_1") (pintype "input"))
    )
    (net (code "83") (name "Net-(LED5-DO)") (class "Default")
      (node (ref "LED5") (pin "3") (pinfunction "DO_3") (pintype "output"))
      (node (ref "LED6") (pin "1") (pinfunction "DI_1") (pintype "input"))
    )
    (net (code "84") (name "Net-(LED6-DO)") (class "Default")
      (node (ref "LED6") (pin "3") (pinfunction "DO_3") (pintype "output"))
      (node (ref "LED7") (pin "1") (pinfunction "DI_1") (pintype "input"))
    )
    (net (code "85") (name "Net-(LED7-DO)") (class "Default")
      (node (ref "LED7") (pin "3") (pinfunction "DO_3") (pintype "output"))
      (node (ref "LED8") (pin "1") (pinfunction "DI_1") (pintype "input"))
    )
    (net (code "86") (name "Net-(LED8-DO)") (class "Default")
      (node (ref "LED8") (pin "3") (pinfunction "DO_3") (pintype "output"))
      (node (ref "LED9") (pin "1") (pinfunction "DI_1") (pintype "input"))
    )
    (net (code "87") (name "Net-(LED10-DI)") (class "Default")
      (node (ref "LED10") (pin "1") (pinfunction "DI_1") (pintype "input"))
      (node (ref "LED9") (pin "3") (pinfunction "DO_3") (pintype "output"))
    )
    (net (code "88") (name "Net-(LED10-DO)") (class "Default")
      (node (ref "LED10") (pin "3") (pinfunction "DO_3") (pintype "output"))
      (node (ref "LED12") (pin "1") (pinfunction "DI_1") (pintype "input"))
    )
    (net (code "89") (name "Net-(LED11-DI)") (class "Default")
      (node (ref "LED11") (pin "1") (pinfunction "DI_1") (pintype "input"))
      (node (ref "LED12") (pin "3") (pinfunction "DO_3") (pintype "output"))
    )
    (net (code "90") (name "Net-(LED11-DO)") (class "Default")
      (node (ref "LED11") (pin "3") (pinfunction "DO_3") (pintype "output"))
      (node (ref "LED13") (pin "1") (pinfunction "DI_1") (pintype "input"))
    )
    (net (code "91") (name "Net-(LED13-DO)") (class "Default")
      (node (ref "LED13") (pin "3") (pinfunction "DO_3") (pintype "output"))
      (node (ref "LED14") (pin "1") (pinfunction "DI_1") (pintype "input"))
    )
    (net (code "92") (name "Net-(LED14-DO)") (class "Default")
      (node (ref "LED14") (pin "3") (pinfunction "DO_3") (pintype "output"))
      (node (ref "LED15") (pin "1") (pinfunction "DI_1") (pintype "input"))
    )
    (net (code "93") (name "Net-(LED15-DO)") (class "Default")
      (node (ref "LED15") (pin "3") (pinfunction "DO_3") (pintype "output"))
      (node (ref "LED16") (pin "1") (pinfunction "DI_1") (pintype "input"))
    )
    (net (code "94") (name "Net-(LED16-DO)") (class "Default")
      (node (ref "LED16") (pin "3") (pinfunction "DO_3") (pintype "output"))
      (node (ref "LED17") (pin "1") (pinfunction "DI_1") (pintype "input"))
    )
    (net (code "95") (name "Net-(LED17-DO)") (class "Default")
      (node (ref "LED17") (pin "3") (pinfunction "DO_3") (pintype "output"))
      (node (ref "LED18") (pin "1") (pinfunction "DI_1") (pintype "input"))
    )
    (net (code "96") (name "Net-(LED18-DO)") (class "Default")
      (node (ref "LED18") (pin "3") (pinfunction "DO_3") (pintype "output"))
      (node (ref "LED19") (pin "1") (pinfunction "DI_1") (pintype "input"))
    )
    (net (code "97") (name "Net-(LED19-DO)") (class "Default")
      (node (ref "LED19") (pin "3") (pinfunction "DO_3") (pintype "output"))
      (node (ref "LED20") (pin "1") (pinfunction "DI_1") (pintype "input"))
    )
    (net (code "98") (name "Net-(LED20-DO)") (class "Default")
      (node (ref "LED20") (pin "3") (pinfunction "DO_3") (pintype "output"))
      (node (ref "LED21") (pin "1") (pinfunction "DI_1") (pintype "input"))
    )
    (net (code "99") (name "Net-(LED21-DO)") (class "Default")
      (node (ref "LED21") (pin "3") (pinfunction "DO_3") (pintype "output"))
      (node (ref "LED22") (pin "1") (pinfunction "DI_1") (pintype "input"))
    )
    (net (code "100") (name "Net-(LED22-DO)") (class "Default")
      (node (ref "LED22") (pin "3") (pinfunction "DO_3") (pintype "output"))
      (node (ref "LED23") (pin "1") (pinfunction "DI_1") (pintype "input"))
    )
    (net (code "101") (name "Net-(LED23-DO)") (class "Default")
      (node (ref "LED23") (pin "3") (pinfunction "DO_3") (pintype "output"))
      (node (ref "LED24") (pin "1") (pinfunction "DI_1") (pintype "input"))
    )
    (net (code "102") (name "Net-(LED24-DO)") (class "Default")
      (node (ref "LED24") (pin "3") (pinfunction "DO_3") (pintype "output"))
      (node (ref "LED25") (pin "1") (pinfunction "DI_1") (pintype "input"))
    )
    (net (code "103") (name "Net-(LED25-DO)") (class "Default")
      (node (ref "LED25") (pin "3") (pinfunction "DO_3") (pintype "output"))
      (node (ref "LED26") (pin "1") (pinfunction "DI_1") (pintype "input"))
    )
    (net (code "104") (name "Net-(LED26-DO)") (class "Default")
      (node (ref "LED26") (pin "3") (pinfunction "DO_3") (pintype "output"))
      (node (ref "LED28") (pin "1") (pinfunction "DI_1") (pintype "input"))
    )
    (net (code "105") (name "Net-(LED27-DI)") (class "Default")
      (node (ref "LED27") (pin "1") (pinfunction "DI_1") (pintype "input"))
      (node (ref "LED28") (pin "3") (pinfunction "DO_3") (pintype "output"))
    )
    (net (code "106") (name "Net-(LED27-DO)") (class "Default")
      (node (ref "LED27") (pin "3") (pinfunction "DO_3") (pintype "output"))
      (node (ref "LED29") (pin "1") (pinfunction "DI_1") (pintype "input"))
    )
    (net (code "107") (name "Net-(LED29-DO)") (class "Default")
      (node (ref "LED29") (pin "3") (pinfunction "DO_3") (pintype "output"))
      (node (ref "LED30") (pin "1") (pinfunction "DI_1") (pintype "input"))
    )
    (net (code "108") (name "Net-(LED30-DO)") (class "Default")
      (node (ref "LED30") (pin "3") (pinfunction "DO_3") (pintype "output"))
      (node (ref "LED31") (pin "1") (pinfunction "DI_1") (pintype "input"))
    )
    (net (code "109") (name "Net-(LED31-DO)") (class "Default")
      (node (ref "LED31") (pin "3") (pinfunction "DO_3") (pintype "output"))
      (node (ref "LED32") (pin "1") (pinfunction "DI_1") (pintype "input"))
    )
    (net (code "110") (name "Net-(LED32-DO)") (class "Default")
      (node (ref "LED32") (pin "3") (pinfunction "DO_3") (pintype "output"))
      (node (ref "LED33") (pin "1") (pinfunction "DI_1") (pintype "input"))
    )
    (net (code "111") (name "Net-(LED33-DO)") (class "Default")
      (node (ref "LED33") (pin "3") (pinfunction "DO_3") (pintype "output"))
      (node (ref "LED34") (pin "1") (pinfunction "DI_1") (pintype "input"))
    )
    (net (code "112") (name "Net-(LED34-DO)") (class "Default")
      (node (ref "LED34") (pin "3") (pinfunction "DO_3") (pintype "output"))
      (node (ref "LED36") (pin "1") (pinfunction "DI_1") (pintype "input"))
    )
    (net (code "113") (name "Net-(LED35-DI)") (class "Default")
      (node (ref "LED35") (pin "1") (pinfunction "DI_1") (pintype "input"))
      (node (ref "LED36") (pin "3") (pinfunction "DO_3") (pintype "output"))
    )
    (net (code "114") (name "Net-(LED35-DO)") (class "Default")
      (node (ref "LED35") (pin "3") (pinfunction "DO_3") (pintype "output"))
      (node (ref "LED37") (pin "1") (pinfunction "DI_1") (pintype "input"))
    )
    (net (code "115") (name "Net-(LED37-DO)") (class "Default")
      (node (ref "LED37") (pin "3") (pinfunction "DO_3") (pintype "output"))
      (node (ref "LED38") (pin "1") (pinfunction "DI_1") (pintype "input"))
    )
    (net (code "116") (name "Net-(LED38-DO)") (class "Default")
      (node (ref "LED38") (pin "3") (pinfunction "DO_3") (pintype "output"))
      (node (ref "LED39") (pin "1") (pinfunction "DI_1") (pintype "input"))
    )
    (net (code "117") (name "Net-(LED39-DO)") (class "Default")
      (node (ref "LED39") (pin "3") (pinfunction "DO_3") (pintype "output"))
      (node (ref "LED40") (pin "1") (pinfunction "DI_1") (pintype "input"))
    )
    (net (code "118") (name "Net-(LED40-DO)") (class "Default")
      (node (ref "LED40") (pin "3") (pinfunction "DO_3") (pintype "output"))
      (node (ref "LED41") (pin "1") (pinfunction "DI_1") (pintype "input"))
    )
    (net (code "119") (name "Net-(LED41-DO)") (class "Default")
      (node (ref "LED41") (pin "3") (pinfunction "DO_3") (pintype "output"))
      (node (ref "LED42") (pin "1") (pinfunction "DI_1") (pintype "input"))
    )
    (net (code "120") (name "Net-(LED42-DO)") (class "Default")
      (node (ref "LED42") (pin "3") (pinfunction "DO_3") (pintype "output"))
      (node (ref "LED44") (pin "1") (pinfunction "DI_1") (pintype "input"))
    )
    (net (code "121") (name "Net-(LED43-DI)") (class "Default")
      (node (ref "LED43") (pin "1") (pinfunction "DI_1") (pintype "input"))
      (node (ref "LED44") (pin "3") (pinfunction "DO_3") (pintype "output"))
    )
    (net (code "122") (name "Net-(LED43-DO)") (class "Default")
      (node (ref "LED43") (pin "3") (pinfunction "DO_3") (pintype "output"))
      (node (ref "LED45") (pin "1") (pinfunction "DI_1") (pintype "input"))
    )
    (net (code "123") (name "Net-(LED45-DO)") (class "Default")
      (node (ref "LED45") (pin "3") (pinfunction "DO_3") (pintype "output"))
      (node (ref "LED46") (pin "1") (pinfunction "DI_1") (pintype "input"))
    )
    (net (code "124") (name "Net-(LED46-DO)") (class "Default")
      (node (ref "LED46") (pin "3") (pinfunction "DO_3") (pintype "output"))
      (node (ref "LED47") (pin "1") (pinfunction "DI_1") (pintype "input"))
    )
    (net (code "125") (name "Net-(LED47-DO)") (class "Default")
      (node (ref "LED47") (pin "3") (pinfunction "DO_3") (pintype "output"))
      (node (ref "LED48") (pin "1") (pinfunction "DI_1") (pintype "input"))
    )
    (net (code "126") (name "Net-(LED48-DO)") (class "Default")
      (node (ref "LED48") (pin "3") (pinfunction "DO_3") (pintype "output"))
      (node (ref "LED49") (pin "1") (pinfunction "DI_1") (pintype "input"))
    )
    (net (code "127") (name "Net-(LED49-DO)") (class "Default")
      (node (ref "LED49") (pin "3") (pinfunction "DO_3") (pintype "output"))
      (node (ref "LED50") (pin "1") (pinfunction "DI_1") (pintype "input"))
    )
    (net (code "128") (name "Net-(LED50-DO)") (class "Default")
      (node (ref "LED50") (pin "3") (pinfunction "DO_3") (pintype "output"))
      (node (ref "LED52") (pin "1") (pinfunction "DI_1") (pintype "input"))
    )
    (net (code "129") (name "Net-(LED51-DI)") (class "Default")
      (node (ref "LED51") (pin "1") (pinfunction "DI_1") (pintype "input"))
      (node (ref "LED52") (pin "3") (pinfunction "DO_3") (pintype "output"))
    )
    (net (code "130") (name "Net-(LED51-DO)") (class "Default")
      (node (ref "LED51") (pin "3") (pinfunction "DO_3") (pintype "output"))
      (node (ref "LED53") (pin "1") (pinfunction "DI_1") (pintype "input"))
    )
    (net (code "131") (name "Net-(LED53-DO)") (class "Default")
      (node (ref "LED53") (pin "3") (pinfunction "DO_3") (pintype "output"))
      (node (ref "LED54") (pin "1") (pinfunction "DI_1") (pintype "input"))
    )
    (net (code "132") (name "Net-(LED54-DO)") (class "Default")
      (node (ref "LED54") (pin "3") (pinfunction "DO_3") (pintype "output"))
      (node (ref "LED55") (pin "1") (pinfunction "DI_1") (pintype "input"))
    )
    (net (code "133") (name "Net-(LED55-DO)") (class "Default")
      (node (ref "LED55") (pin "3") (pinfunction "DO_3") (pintype "output"))
      (node (ref "LED56") (pin "1") (pinfunction "DI_1") (pintype "input"))
    )
    (net (code "134") (name "Net-(PTC1-Pad2)") (class "Default")
      (node (ref "PTC1") (pin "2") (pinfunction "2_2") (pintype "passive"))
      (node (ref "X3") (pin "VBUS") (pinfunction "VBUS_VBUS") (pintype "power_in"))
    )
    (net (code "135") (name "ROW0") (class "Default")
      (node (ref "D1") (pin "A") (pinfunction "A_A") (pintype "passive"))
      (node (ref "D17") (pin "A") (pinfunction "A_A") (pintype "passive"))
      (node (ref "D18") (pin "A") (pinfunction "A_A") (pintype "passive"))
      (node (ref "D19") (pin "A") (pinfunction "A_A") (pintype "passive"))
      (node (ref "D2") (pin "A") (pinfunction "A_A") (pintype "passive"))
      (node (ref "D20") (pin "A") (pinfunction "A_A") (pintype "passive"))
      (node (ref "D3") (pin "A") (pinfunction "A_A") (pintype "passive"))
      (node (ref "D9") (pin "A") (pinfunction "A_A") (pintype "passive"))
      (node (ref "IC4") (pin "14") (pinfunction "PA09/I2C/I9/AIN9/SERCOM0.1+2.0/I2SFS0_14") (pintype "bidirectional"))
    )
    (net (code "136") (name "ROW1") (class "Default")
      (node (ref "D21") (pin "A") (pinfunction "A_A") (pintype "passive"))
      (node (ref "D22") (pin "A") (pinfunction "A_A") (pintype "passive"))
      (node (ref "D23") (pin "A") (pinfunction "A_A") (pintype "passive"))
      (node (ref "D24") (pin "A") (pinfunction "A_A") (pintype "passive"))
      (node (ref "D4") (pin "A") (pinfunction "A_A") (pintype "passive"))
      (node (ref "D5") (pin "A") (pinfunction "A_A") (pintype "passive"))
      (node (ref "D6") (pin "A") (pinfunction "A_A") (pintype "passive"))
      (node (ref "D7") (pin "A") (pinfunction "A_A") (pintype "passive"))
      (node (ref "IC4") (pin "15") (pinfunction "PA10/I10/AIN10/SERCOM0+2.2/I2SCK_15") (pintype "bidirectional"))
    )
    (net (code "137") (name "ROW2") (class "Default")
      (node (ref "D10") (pin "A") (pinfunction "A_A") (pintype "passive"))
      (node (ref "D11") (pin "A") (pinfunction "A_A") (pintype "passive"))
      (node (ref "D12") (pin "A") (pinfunction "A_A") (pintype "passive"))
      (node (ref "D25") (pin "A") (pinfunction "A_A") (pintype "passive"))
      (node (ref "D26") (pin "A") (pinfunction "A_A") (pintype "passive"))
      (node (ref "D27") (pin "A") (pinfunction "A_A") (pintype "passive"))
      (node (ref "D28") (pin "A") (pinfunction "A_A") (pintype "passive"))
      (node (ref "D8") (pin "A") (pinfunction "A_A") (pintype "passive"))
      (node (ref "IC4") (pin "16") (pinfunction "PA11/I11/AIN11/SERCOM0+2.3/I2SDO_16") (pintype "bidirectional"))
    )
    (net (code "138") (name "ROW3") (class "Default")
      (node (ref "D13") (pin "A") (pinfunction "A_A") (pintype "passive"))
      (node (ref "D14") (pin "A") (pinfunction "A_A") (pintype "passive"))
      (node (ref "D15") (pin "A") (pinfunction "A_A") (pintype "passive"))
      (node (ref "D16") (pin "A") (pinfunction "A_A") (pintype "passive"))
      (node (ref "D29") (pin "A") (pinfunction "A_A") (pintype "passive"))
      (node (ref "D30") (pin "A") (pinfunction "A_A") (pintype "passive"))
      (node (ref "D31") (pin "A") (pinfunction "A_A") (pintype "passive"))
      (node (ref "D32") (pin "A") (pinfunction "A_A") (pintype "passive"))
      (node (ref "IC4") (pin "21") (pinfunction "PA12/I12/I2C/SERCOM2.0+4.1_21") (pintype "bidirectional"))
    )
    (net (code "139") (name "ROW4") (class "Default")
      (node (ref "D33") (pin "A") (pinfunction "A_A") (pintype "passive"))
      (node (ref "D35") (pin "A") (pinfunction "A_A") (pintype "passive"))
      (node (ref "D36") (pin "A") (pinfunction "A_A") (pintype "passive"))
      (node (ref "D37") (pin "A") (pinfunction "A_A") (pintype "passive"))
      (node (ref "D46") (pin "A") (pinfunction "A_A") (pintype "passive"))
      (node (ref "D47") (pin "A") (pinfunction "A_A") (pintype "passive"))
      (node (ref "D48") (pin "A") (pinfunction "A_A") (pintype "passive"))
      (node (ref "D49") (pin "A") (pinfunction "A_A") (pintype "passive"))
      (node (ref "IC4") (pin "22") (pinfunction "PA13/I13/I2C/SERCOM2.1+4.0_22") (pintype "bidirectional"))
    )
    (net (code "140") (name "ROW5") (class "Default")
      (node (ref "D38") (pin "A") (pinfunction "A_A") (pintype "passive"))
      (node (ref "D39") (pin "A") (pinfunction "A_A") (pintype "passive"))
      (node (ref "D40") (pin "A") (pinfunction "A_A") (pintype "passive"))
      (node (ref "D41") (pin "A") (pinfunction "A_A") (pintype "passive"))
      (node (ref "D50") (pin "A") (pinfunction "A_A") (pintype "passive"))
      (node (ref "D51") (pin "A") (pinfunction "A_A") (pintype "passive"))
      (node (ref "D52") (pin "A") (pinfunction "A_A") (pintype "passive"))
      (node (ref "D53") (pin "A") (pinfunction "A_A") (pintype "passive"))
      (node (ref "IC4") (pin "23") (pinfunction "PA14/I14/SERCOM2+4.2_23") (pintype "bidirectional"))
    )
    (net (code "141") (name "ROW6") (class "Default")
      (node (ref "D42") (pin "A") (pinfunction "A_A") (pintype "passive"))
      (node (ref "D43") (pin "A") (pinfunction "A_A") (pintype "passive"))
      (node (ref "D44") (pin "A") (pinfunction "A_A") (pintype "passive"))
      (node (ref "D45") (pin "A") (pinfunction "A_A") (pintype "passive"))
      (node (ref "D54") (pin "A") (pinfunction "A_A") (pintype "passive"))
      (node (ref "D55") (pin "A") (pinfunction "A_A") (pintype "passive"))
      (node (ref "D56") (pin "A") (pinfunction "A_A") (pintype "passive"))
      (node (ref "D57") (pin "A") (pinfunction "A_A") (pintype "passive"))
      (node (ref "IC4") (pin "24") (pinfunction "PA15/I15/SERCOM2+4.3_24") (pintype "bidirectional"))
    )
    (net (code "142") (name "SCL") (class "Default")
      (node (ref "IC4") (pin "8") (pinfunction "PB09/I9/AIN3/SERCOM4.1_8") (pintype "bidirectional"))
      (node (ref "JP3") (pin "4") (pinfunction "4_4") (pintype "passive"))
      (node (ref "JP4") (pin "4") (pinfunction "4_4") (pintype "passive"))
      (node (ref "R2") (pin "4") (pinfunction "1_4") (pintype "passive"))
    )
    (net (code "143") (name "SDA") (class "Default")
      (node (ref "IC4") (pin "7") (pinfunction "PB08/I8/AIN2/SERCOM4.0_7") (pintype "bidirectional"))
      (node (ref "JP3") (pin "5") (pinfunction "5_5") (pintype "passive"))
      (node (ref "JP4") (pin "5") (pinfunction "5_5") (pintype "passive"))
      (node (ref "R2") (pin "3") (pinfunction "1_3") (pintype "passive"))
    )
    (net (code "144") (name "SWCLK") (class "Default")
      (node (ref "IC4") (pin "45") (pinfunction "PA30/I14/SECOM1.2/SWCLK_45") (pintype "bidirectional"))
      (node (ref "R11") (pin "1") (pinfunction "1_1") (pintype "passive"))
    )
    (net (code "145") (name "SWDIO") (class "Default")
      (node (ref "IC4") (pin "46") (pinfunction "PA31/I15/SECOM1.3/SWDIO_46") (pintype "bidirectional"))
    )
    (net (code "146") (name "VBUS") (class "Default")
      (node (ref "D34") (pin "A") (pinfunction "A_A") (pintype "passive"))
      (node (ref "PTC1") (pin "1") (pinfunction "1_1") (pintype "passive"))
    )
    (net (code "147") (name "VDD") (class "Default")
      (node (ref "C1") (pin "2") (pinfunction "2_2") (pintype "passive"))
      (node (ref "C2") (pin "2") (pinfunction "2_2") (pintype "passive"))
      (node (ref "C3") (pin "2") (pinfunction "2_2") (pintype "passive"))
      (node (ref "C4") (pin "2") (pinfunction "2_2") (pintype "passive"))
      (node (ref "C5") (pin "2") (pinfunction "2_2") (pintype "passive"))
      (node (ref "C6") (pin "2") (pinfunction "2_2") (pintype "passive"))
      (node (ref "C9") (pin "1") (pinfunction "1_1") (pintype "passive"))
      (node (ref "D34") (pin "C") (pinfunction "C_C") (pintype "passive"))
      (node (ref "IC2") (pin "5") (pinfunction "VCC_5") (pintype "power_in"))
      (node (ref "JP3") (pin "2") (pinfunction "2_2") (pintype "passive"))
      (node (ref "JP4") (pin "2") (pinfunction "2_2") (pintype "passive"))
      (node (ref "LED1") (pin "2") (pinfunction "VDD_2") (pintype "power_in"))
      (node (ref "LED10") (pin "2") (pinfunction "VDD_2") (pintype "power_in"))
      (node (ref "LED11") (pin "2") (pinfunction "VDD_2") (pintype "power_in"))
      (node (ref "LED12") (pin "2") (pinfunction "VDD_2") (pintype "power_in"))
      (node (ref "LED13") (pin "2") (pinfunction "VDD_2") (pintype "power_in"))
      (node (ref "LED14") (pin "2") (pinfunction "VDD_2") (pintype "power_in"))
      (node (ref "LED15") (pin "2") (pinfunction "VDD_2") (pintype "power_in"))
      (node (ref "LED16") (pin "2") (pinfunction "VDD_2") (pintype "power_in"))
      (node (ref "LED17") (pin "2") (pinfunction "VDD_2") (pintype "power_in"))
      (node (ref "LED18") (pin "2") (pinfunction "VDD_2") (pintype "power_in"))
      (node (ref "LED19") (pin "2") (pinfunction "VDD_2") (pintype "power_in"))
      (node (ref "LED2") (pin "2") (pinfunction "VDD_2") (pintype "power_in"))
      (node (ref "LED20") (pin "2") (pinfunction "VDD_2") (pintype "power_in"))
      (node (ref "LED21") (pin "2") (pinfunction "VDD_2") (pintype "power_in"))
      (node (ref "LED22") (pin "2") (pinfunction "VDD_2") (pintype "power_in"))
      (node (ref "LED23") (pin "2") (pinfunction "VDD_2") (pintype "power_in"))
      (node (ref "LED24") (pin "2") (pinfunction "VDD_2") (pintype "power_in"))
      (node (ref "LED25") (pin "2") (pinfunction "VDD_2") (pintype "power_in"))
      (node (ref "LED26") (pin "2") (pinfunction "VDD_2") (pintype "power_in"))
      (node (ref "LED27") (pin "2") (pinfunction "VDD_2") (pintype "power_in"))
      (node (ref "LED28") (pin "2") (pinfunction "VDD_2") (pintype "power_in"))
      (node (ref "LED29") (pin "2") (pinfunction "VDD_2") (pintype "power_in"))
      (node (ref "LED3") (pin "2") (pinfunction "VDD_2") (pintype "power_in"))
      (node (ref "LED30") (pin "2") (pinfunction "VDD_2") (pintype "power_in"))
      (node (ref "LED31") (pin "2") (pinfunction "VDD_2") (pintype "power_in"))
      (node (ref "LED32") (pin "2") (pinfunction "VDD_2") (pintype "power_in"))
      (node (ref "LED33") (pin "2") (pinfunction "VDD_2") (pintype "power_in"))
      (node (ref "LED34") (pin "2") (pinfunction "VDD_2") (pintype "power_in"))
      (node (ref "LED35") (pin "2") (pinfunction "VDD_2") (pintype "power_in"))
      (node (ref "LED36") (pin "2") (pinfunction "VDD_2") (pintype "power_in"))
      (node (ref "LED37") (pin "2") (pinfunction "VDD_2") (pintype "power_in"))
      (node (ref "LED38") (pin "2") (pinfunction "VDD_2") (pintype "power_in"))
      (node (ref "LED39") (pin "2") (pinfunction "VDD_2") (pintype "power_in"))
      (node (ref "LED4") (pin "2") (pinfunction "VDD_2") (pintype "power_in"))
      (node (ref "LED40") (pin "2") (pinfunction "VDD_2") (pintype "power_in"))
      (node (ref "LED41") (pin "2") (pinfunction "VDD_2") (pintype "power_in"))
      (node (ref "LED42") (pin "2") (pinfunction "VDD_2") (pintype "power_in"))
      (node (ref "LED43") (pin "2") (pinfunction "VDD_2") (pintype "power_in"))
      (node (ref "LED44") (pin "2") (pinfunction "VDD_2") (pintype "power_in"))
      (node (ref "LED45") (pin "2") (pinfunction "VDD_2") (pintype "power_in"))
      (node (ref "LED46") (pin "2") (pinfunction "VDD_2") (pintype "power_in"))
      (node (ref "LED47") (pin "2") (pinfunction "VDD_2") (pintype "power_in"))
      (node (ref "LED48") (pin "2") (pinfunction "VDD_2") (pintype "power_in"))
      (node (ref "LED49") (pin "2") (pinfunction "VDD_2") (pintype "power_in"))
      (node (ref "LED5") (pin "2") (pinfunction "VDD_2") (pintype "power_in"))
      (node (ref "LED50") (pin "2") (pinfunction "VDD_2") (pintype "power_in"))
      (node (ref "LED51") (pin "2") (pinfunction "VDD_2") (pintype "power_in"))
      (node (ref "LED52") (pin "2") (pinfunction "VDD_2") (pintype "power_in"))
      (node (ref "LED53") (pin "2") (pinfunction "VDD_2") (pintype "power_in"))
      (node (ref "LED54") (pin "2") (pinfunction "VDD_2") (pintype "power_in"))
      (node (ref "LED55") (pin "2") (pinfunction "VDD_2") (pintype "power_in"))
      (node (ref "LED56") (pin "2") (pinfunction "VDD_2") (pintype "power_in"))
      (node (ref "LED6") (pin "2") (pinfunction "VDD_2") (pintype "power_in"))
      (node (ref "LED7") (pin "2") (pinfunction "VDD_2") (pintype "power_in"))
      (node (ref "LED8") (pin "2") (pinfunction "VDD_2") (pintype "power_in"))
      (node (ref "LED9") (pin "2") (pinfunction "VDD_2") (pintype "power_in"))
      (node (ref "U1") (pin "1") (pinfunction "IN_1") (pintype "power_in"))
      (node (ref "U1") (pin "3") (pinfunction "EN_3") (pintype "input"))
    )
    (net (code "148") (name "VSS") (class "Default")
      (node (ref "IC4") (pin "5") (pinfunction "GNDA_5") (pintype "power_in"))
    )
    (net (code "149") (name "VSW") (class "Default")
      (node (ref "IC4") (pin "43") (pinfunction "VSW_43") (pintype "power_in"))
    )
    (net (code "150") (name "unconnected-(IC4A-PA16{slash}I2C{slash}I0{slash}SERCOM1.0+3.1-Pad25)") (class "Default")
      (node (ref "IC4") (pin "25") (pinfunction "PA16/I2C/I0/SERCOM1.0+3.1_25") (pintype "bidirectional"))
    )
    (net (code "151") (name "unconnected-(IC4A-PA17{slash}I2C{slash}I1{slash}SERCOM1.1+3.0-Pad26)") (class "Default")
      (node (ref "IC4") (pin "26") (pinfunction "PA17/I2C/I1/SERCOM1.1+3.0_26") (pintype "bidirectional"))
    )
    (net (code "152") (name "unconnected-(IC4A-PA18{slash}I2{slash}SERCOM1+3.2-Pad27)") (class "Default")
      (node (ref "IC4") (pin "27") (pinfunction "PA18/I2/SERCOM1+3.2_27") (pintype "bidirectional"))
    )
    (net (code "153") (name "unconnected-(IC4A-PA19{slash}I3{slash}SERCOM1+3.3-Pad28)") (class "Default")
      (node (ref "IC4") (pin "28") (pinfunction "PA19/I3/SERCOM1+3.3_28") (pintype "bidirectional"))
    )
    (net (code "154") (name "unconnected-(IC4A-PA20{slash}I4{slash}SERCOM3+5.2{slash}I2SFS0-Pad29)") (class "Default")
      (node (ref "IC4") (pin "29") (pinfunction "PA20/I4/SERCOM3+5.2/I2SFS0_29") (pintype "bidirectional"))
    )
    (net (code "155") (name "unconnected-(IC4A-PA21{slash}I5{slash}SERCOM3+5.3{slash}I2SDO-Pad30)") (class "Default")
      (node (ref "IC4") (pin "30") (pinfunction "PA21/I5/SERCOM3+5.3/I2SDO_30") (pintype "bidirectional"))
    )
    (net (code "156") (name "unconnected-(IC4A-PA22{slash}I2C{slash}I6{slash}SERCOM3.0+5.1{slash}I2SDI-Pad31)") (class "Default")
      (node (ref "IC4") (pin "31") (pinfunction "PA22/I2C/I6/SERCOM3.0+5.1/I2SDI_31") (pintype "bidirectional"))
    )
    (net (code "157") (name "unconnected-(IC4A-PB10{slash}I10{slash}SERCOM4.2{slash}I2SDI-Pad19)") (class "Default")
      (node (ref "IC4") (pin "19") (pinfunction "PB10/I10/SERCOM4.2/I2SDI_19") (pintype "bidirectional"))
    )
    (net (code "158") (name "unconnected-(IC4A-PB11{slash}I11{slash}SERCOM4.3{slash}I2SFS1-Pad20)") (class "Default")
      (node (ref "IC4") (pin "20") (pinfunction "PB11/I11/SERCOM4.3/I2SFS1_20") (pintype "bidirectional"))
    )
    (net (code "159") (name "unconnected-(IC4A-PB22{slash}I6{slash}SERCOM1+5.2-Pad37)") (class "Default")
      (node (ref "IC4") (pin "37") (pinfunction "PB22/I6/SERCOM1+5.2_37") (pintype "bidirectional"))
    )
    (net (code "160") (name "unconnected-(IC4A-PB23{slash}I7{slash}SERCOM1+5.3-Pad38)") (class "Default")
      (node (ref "IC4") (pin "38") (pinfunction "PB23/I7/SERCOM1+5.3_38") (pintype "bidirectional"))
    )
    (net (code "161") (name "unconnected-(J2-Pad1)") (class "Default")
      (node (ref "J2") (pin "1") (pinfunction "1_1") (pintype "bidirectional"))
    )
    (net (code "162") (name "unconnected-(J2-Pad3)") (class "Default")
      (node (ref "J2") (pin "3") (pinfunction "3_3") (pintype "bidirectional"))
    )
    (net (code "163") (name "unconnected-(L2-CKO-Pad2)") (class "Default")
      (node (ref "L2") (pin "2") (pinfunction "CKO_2") (pintype "output"))
    )
    (net (code "164") (name "unconnected-(L2-DO-Pad1)") (class "Default")
      (node (ref "L2") (pin "1") (pinfunction "DO_1") (pintype "output"))
    )
    (net (code "165") (name "unconnected-(LED56-DO-Pad3)") (class "Default")
      (node (ref "LED56") (pin "3") (pinfunction "DO_3") (pintype "output"))
    )
    (net (code "166") (name "unconnected-(U1-P4-Pad4)") (class "Default")
      (node (ref "U1") (pin "4") (pinfunction "P4_4") (pintype "bidirectional"))
    )
    (net (code "167") (name "unconnected-(X3-PadID)") (class "Default")
      (node (ref "X3") (pin "ID") (pinfunction "ID_ID") (pintype "bidirectional"))
    )
    (net (code "168") (name "~{RESET}") (class "Default")
      (node (ref "C15") (pin "2") (pinfunction "2_2") (pintype "passive"))
      (node (ref "IC4") (pin "40") (pinfunction "/RESET_40") (pintype "bidirectional"))
      (node (ref "R2") (pin "1") (pinfunction "1_1") (pintype "passive"))
      (node (ref "SW1") (pin "1") (pinfunction "P_1") (pintype "passive"))
      (node (ref "SW1") (pin "3") (pinfunction "P1_3") (pintype "passive"))
    )
  )
)
